# Arduino_DUE_V02b_1.net
KiCad netlist of a schematic drawn in Altium Designer
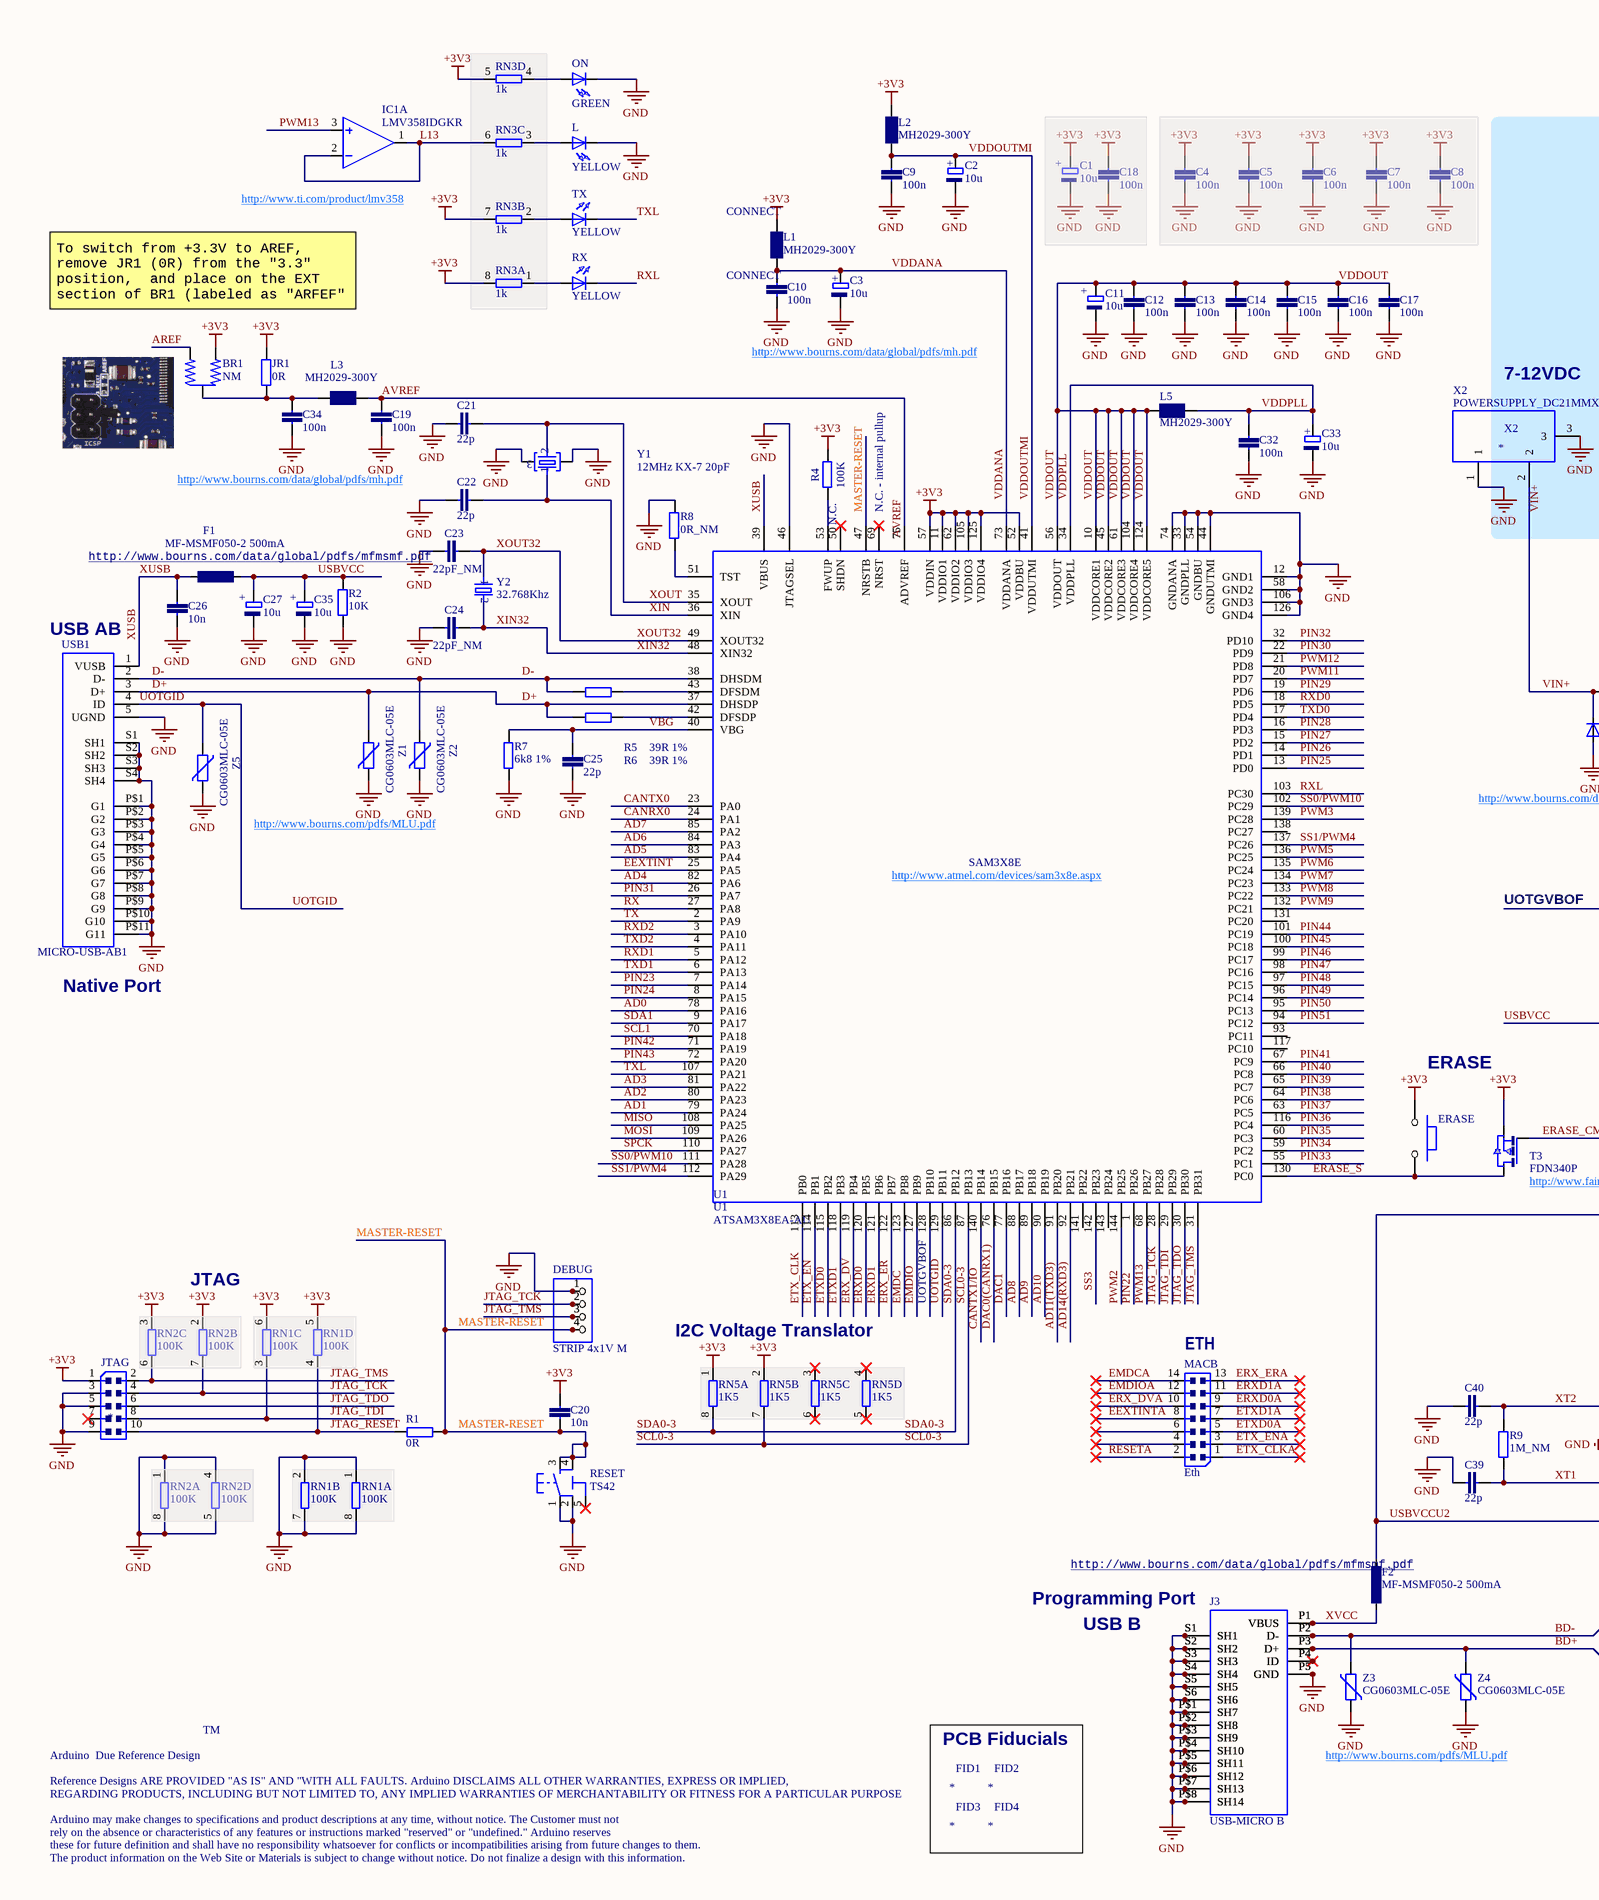
[diagram p0: Arduino_DUE_V02b_1.SchDoc, left]
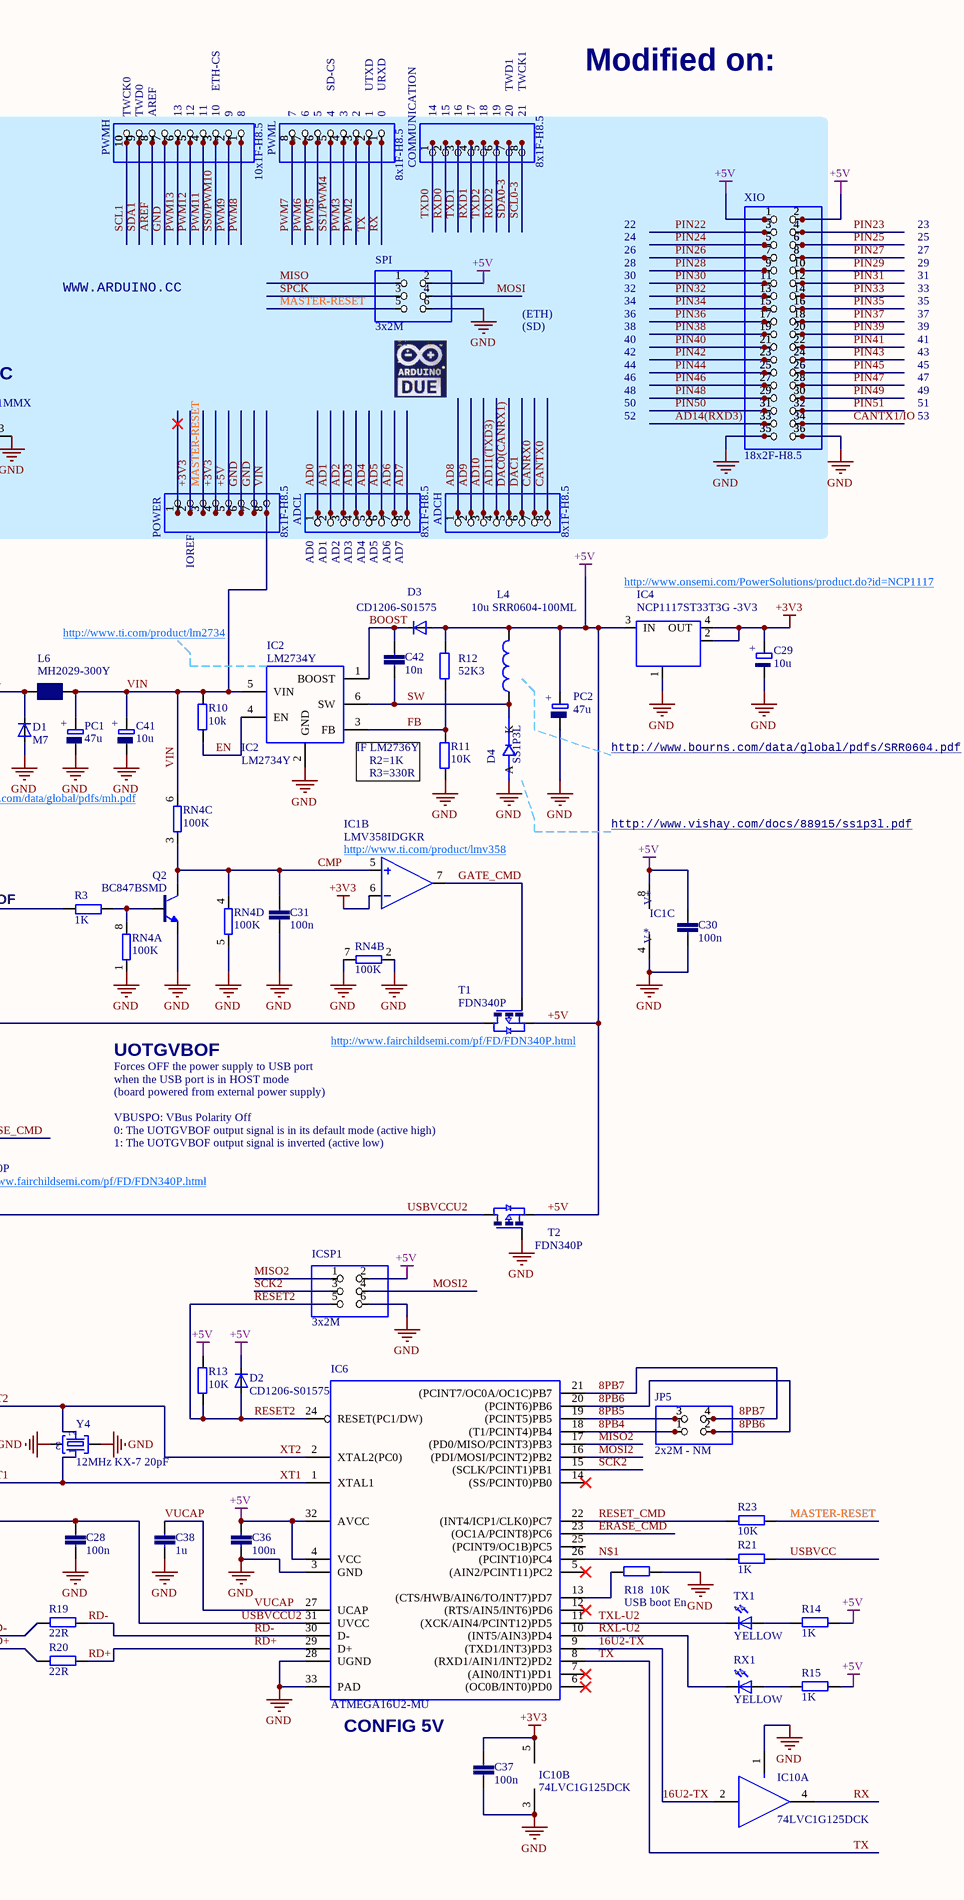
[diagram p1: Arduino_DUE_V02b_1.SchDoc, right]

(export (version "E")
  (design (tool "Eeschema 10.0.6"))
  (components
    (comp (ref "ADCH") (value "8x1F-H8.5") (footprint "1X08") (libsource (lib "SmartPrj") (part "PINHD-1X8")))
    (comp (ref "ADCL") (value "8x1F-H8.5") (footprint "1X08") (libsource (lib "SmartPrj") (part "PINHD-1X8")))
    (comp (ref "BR1") (value "NM") (footprint "J0402") (libsource (lib "bibaja") (part "J0402")))
    (comp (ref "C1") (value "10u") (footprint "SMC_B") (libsource (lib "") (part "CPOL-EUSMCB_1")))
    (comp (ref "C2") (value "10u") (footprint "SMC_B") (libsource (lib "rcl") (part "CPOL-EUSMCB")))
    (comp (ref "C3") (value "10u") (footprint "SMC_B") (libsource (lib "rcl") (part "CPOL-EUSMCB")))
    (comp (ref "C4") (value "100n") (footprint "C0402") (libsource (lib "") (part "C-EUC0402_2")))
    (comp (ref "C5") (value "100n") (footprint "C0402") (libsource (lib "") (part "C-EUC0402_2")))
    (comp (ref "C6") (value "100n") (footprint "C0402") (libsource (lib "") (part "C-EUC0402_2")))
    (comp (ref "C7") (value "100n") (footprint "C0402") (libsource (lib "") (part "C-EUC0402_2")))
    (comp (ref "C8") (value "100n") (footprint "C0402") (libsource (lib "") (part "C-EUC0402_2")))
    (comp (ref "C9") (value "100n") (footprint "C0402") (libsource (lib "") (part "C-EUC0402_2")))
    (comp (ref "C10") (value "100n") (footprint "C0402") (libsource (lib "") (part "C-EUC0402_2")))
    (comp (ref "C11") (value "10u") (footprint "SMC_B") (libsource (lib "") (part "CPOL-EUSMCB_1")))
    (comp (ref "C12") (value "100n") (footprint "C0402") (libsource (lib "") (part "C-EUC0402_2")))
    (comp (ref "C13") (value "100n") (footprint "C0402") (libsource (lib "") (part "C-EUC0402_2")))
    (comp (ref "C14") (value "100n") (footprint "C0402") (libsource (lib "") (part "C-EUC0402_2")))
    (comp (ref "C15") (value "100n") (footprint "C0402") (libsource (lib "") (part "C-EUC0402_2")))
    (comp (ref "C16") (value "100n") (footprint "C0402") (libsource (lib "") (part "C-EUC0402_2")))
    (comp (ref "C17") (value "100n") (footprint "C0402") (libsource (lib "") (part "C-EUC0402_2")))
    (comp (ref "C18") (value "100n") (footprint "C0402") (libsource (lib "") (part "C-EUC0402_2")))
    (comp (ref "C19") (value "100n") (footprint "C0402") (libsource (lib "") (part "C-EUC0402_1")))
    (comp (ref "C20") (value "10n") (footprint "C0402") (libsource (lib "") (part "C-EUC0402_1")))
    (comp (ref "C21") (value "22p") (footprint "C0402") (libsource (lib "") (part "C-EUC0402_3")))
    (comp (ref "C22") (value "22p") (footprint "C0402") (libsource (lib "") (part "C-EUC0402_3")))
    (comp (ref "C23") (value "22pF_NM") (footprint "C0402") (libsource (lib "") (part "C-EUC0402_3")))
    (comp (ref "C24") (value "22pF_NM") (footprint "C0402") (libsource (lib "") (part "C-EUC0402_3")))
    (comp (ref "C25") (value "22p") (footprint "C0402") (libsource (lib "SmartPrj") (part "C-EUC0402")))
    (comp (ref "C26") (value "10n") (footprint "C0402") (libsource (lib "SmartPrj") (part "C-EUC0402")))
    (comp (ref "C27") (value "10u") (footprint "SMC_B") (libsource (lib "") (part "CPOL-EUSMCB_1")))
    (comp (ref "C28") (value "100n") (footprint "C0402") (libsource (lib "SmartPrj") (part "C-EUC0402")))
    (comp (ref "C29") (value "10u") (footprint "SMC_B") (libsource (lib "") (part "CPOL-EUSMCB_1")))
    (comp (ref "C30") (value "100n") (footprint "C0402") (libsource (lib "") (part "C-EUC0402_2")))
    (comp (ref "C31") (value "100n") (footprint "C0402") (libsource (lib "") (part "C-EUC0402_2")))
    (comp (ref "C32") (value "100n") (footprint "C0402") (libsource (lib "") (part "C-EUC0402_2")))
    (comp (ref "C33") (value "10u") (footprint "SMC_B") (libsource (lib "rcl") (part "CPOL-EUSMCB")))
    (comp (ref "C34") (value "100n") (footprint "C0402") (libsource (lib "") (part "C-EUC0402_1")))
    (comp (ref "C35") (value "10u") (footprint "SMC_B") (libsource (lib "") (part "CPOL-EUSMCB_1")))
    (comp (ref "C36") (value "100n") (footprint "C0402") (libsource (lib "SmartPrj") (part "C-EUC0402")))
    (comp (ref "C37") (value "100n") (footprint "C0402") (libsource (lib "SmartPrj") (part "C-EUC0402")))
    (comp (ref "C38") (value "1u") (footprint "C0402") (libsource (lib "SmartPrj") (part "C-EUC0402")))
    (comp (ref "C39") (value "22p") (footprint "C0402") (libsource (lib "") (part "C-EUC0402_3")))
    (comp (ref "C40") (value "22p") (footprint "C0402") (libsource (lib "") (part "C-EUC0402_3")))
    (comp (ref "C41") (value "10u") (footprint "SMC_B") (libsource (lib "") (part "CPOL-EUSMCB_2")))
    (comp (ref "C42") (value "10n") (footprint "C0603-ROUND") (libsource (lib "SmartPrj") (part "C-EUC0603")))
    (comp (ref "COMMUNICATION")
      (value "8x1F-H8.5")
      (footprint "1X08")
      (libsource (lib "SmartPrj") (part "PINHD-1X8"))
    )
    (comp (ref "D1") (value "M7") (footprint "SMB") (libsource (lib "diode") (part "DIODE-SMB")))
    (comp (ref "D2")
      (value "CD1206-S01575")
      (footprint "MINIMELF")
      (libsource (lib "diode") (part "DIODE-MINIMELF"))
    )
    (comp (ref "D3")
      (value "CD1206-S01575")
      (footprint "MINIMELF")
      (libsource (lib "diode") (part "DIODE-MINIMELF"))
    )
    (comp (ref "D4") (value "SS1P3L") (footprint "DO220AAL") (libsource (lib "SmartPrj") (part "SS1P3L")))
    (comp (ref "DEBUG")
      (value "STRIP 4x1V M")
      (footprint "1X04")
      (libsource (lib "pinhead") (part "PINHD-1X4"))
    )
    (comp (ref "ERASE") (value "~") (footprint "SMD_157SW") (libsource (lib "SmartPrj") (part "MYSMD_PB157")))
    (comp (ref "F1")
      (value "MF-MSMF050-2 500mA")
      (footprint "L1812")
      (libsource (lib "rcl") (part "L-EUL1812"))
    )
    (comp (ref "F2")
      (value "MF-MSMF050-2 500mA")
      (footprint "L1812")
      (libsource (lib "") (part "L-EUL1812_1"))
    )
    (comp (ref "FID1")
      (value "*")
      (footprint "FIDUCIA-MOUNT")
      (libsource (lib "SmartPrj") (part "FIDUCIALMOUNT"))
    )
    (comp (ref "FID2")
      (value "*")
      (footprint "FIDUCIA-MOUNT")
      (libsource (lib "SmartPrj") (part "FIDUCIALMOUNT"))
    )
    (comp (ref "FID3")
      (value "*")
      (footprint "FIDUCIA-MOUNT")
      (libsource (lib "SmartPrj") (part "FIDUCIALMOUNT"))
    )
    (comp (ref "FID4")
      (value "*")
      (footprint "FIDUCIA-MOUNT")
      (libsource (lib "SmartPrj") (part "FIDUCIALMOUNT"))
    )
    (comp (ref "IC1") (value "LMV358IDGKR") (footprint "MSOP08") (libsource (lib "") (part "LMV358MMX_1")))
    (comp (ref "IC2") (value "LM2734Y") (footprint "SOT23-6") (libsource (lib "SmartPrj") (part "LM2736Y")))
    (comp (ref "IC4")
      (value "NCP1117ST33T3G -3V3")
      (footprint "SOT223")
      (libsource (lib "linear") (part "MC33269ST-3.3T3"))
    )
    (comp (ref "IC6")
      (value "ATMEGA16U2-MU")
      (footprint "MLF32")
      (libsource (lib "SmartPrj") (part "ATMEGA16U2-MU"))
    )
    (comp (ref "IC10")
      (value "74LVC1G125DCK")
      (footprint "SC70-5")
      (libsource (lib "") (part "74LVC1G125DCK_1"))
    )
    (comp (ref "ICSP1") (value "3x2M") (footprint "2X03") (libsource (lib "SmartPrj") (part "PINHD-2X3")))
    (comp (ref "J3")
      (value "USB-MICRO B")
      (footprint "CON2_USB_MICRO_B_AT")
      (libsource (lib "SmartPrj") (part "MYCON2_USB-MINI-B"))
    )
    (comp (ref "JP5") (value "2x2M - NM") (footprint "2X02") (libsource (lib "SmartPrj") (part "PINHD-2X2")))
    (comp (ref "JR1") (value "0R") (footprint "R0402") (libsource (lib "") (part "R-EU_R0402_2")))
    (comp (ref "JTAG")
      (value "*")
      (footprint "PINHEAD_2X05_127")
      (libsource (lib "Arduino_Wifi_shield_v018_tG") (part "PINHEAD_PINHD-2X5PASSO127"))
    )
    (comp (ref "L")
      (value "YELLOW")
      (footprint "CHIP-LED0805")
      (libsource (lib "") (part "LEDCHIP-LED0805_2"))
    )
    (comp (ref "L1") (value "MH2029-300Y") (footprint "0805") (libsource (lib "") (part "WE-CBF_0805_1")))
    (comp (ref "L2") (value "MH2029-300Y") (footprint "0805") (libsource (lib "") (part "WE-CBF_0805_1")))
    (comp (ref "L3") (value "MH2029-300Y") (footprint "0805") (libsource (lib "") (part "WE-CBF_0805_2")))
    (comp (ref "L4")
      (value "10u SRR0604-100ML")
      (footprint "SRR0604")
      (libsource (lib "SmartPrj") (part "L-USSRR0604"))
    )
    (comp (ref "L5") (value "MH2029-300Y") (footprint "0805") (libsource (lib "") (part "WE-CBF_0805_2")))
    (comp (ref "L6")
      (value "MH2029-300Y")
      (footprint "0805")
      (libsource (lib "wuerth-elektronik") (part "WE-CBF_0805"))
    )
    (comp (ref "MACB")
      (value "Eth")
      (footprint "PINHEAD_2X07_127")
      (libsource (lib "Arduino_Wifi_shield_v018_tG") (part "PINHEAD_PINHD-2X7PASSO127"))
    )
    (comp (ref "ON")
      (value "GREEN")
      (footprint "CHIP-LED0805")
      (libsource (lib "") (part "LEDCHIP-LED0805_2"))
    )
    (comp (ref "PC1") (value "47u") (footprint "PANASONIC_D") (libsource (lib "rcl") (part "CPOL-EUD")))
    (comp (ref "PC2") (value "47u") (footprint "PANASONIC_D") (libsource (lib "rcl") (part "CPOL-EUD")))
    (comp (ref "POWER")
      (value "8x1F-H8.5")
      (footprint "1X08")
      (libsource (lib "SmartPrj") (part "PINHD-1X8"))
    )
    (comp (ref "PWMH")
      (value "10x1F-H8.5")
      (footprint "1X10")
      (libsource (lib "SmartPrj") (part "PINHD-1X10"))
    )
    (comp (ref "PWML") (value "8x1F-H8.5") (footprint "1X08") (libsource (lib "SmartPrj") (part "PINHD-1X8")))
    (comp (ref "Q2")
      (value "BC847BSMD")
      (footprint "SOT23")
      (libsource (lib "transistor-npn") (part "BC847BSMD"))
    )
    (comp (ref "R1") (value "0R") (footprint "R0402") (libsource (lib "") (part "R-EU_R0402_2")))
    (comp (ref "R2") (value "10K") (footprint "R0402") (libsource (lib "") (part "R-EU_R0402_1")))
    (comp (ref "R3") (value "1K") (footprint "R0402") (libsource (lib "") (part "R-EU_R0402_2")))
    (comp (ref "R4") (value "100K") (footprint "R0402") (libsource (lib "SmartPrj") (part "R-EU_R0402")))
    (comp (ref "R5") (value "39R 1%") (footprint "R0402") (libsource (lib "") (part "R-EU_R0402_2")))
    (comp (ref "R6") (value "39R 1%") (footprint "R0402") (libsource (lib "") (part "R-EU_R0402_2")))
    (comp (ref "R7")
      (value "6k8 1%")
      (footprint "R0603-ROUND")
      (libsource (lib "SmartPrj") (part "R-EU_R0603"))
    )
    (comp (ref "R8") (value "0R_NM") (footprint "R0402") (libsource (lib "") (part "R-EU_R0402_2")))
    (comp (ref "R9") (value "1M_NM") (footprint "R0402") (libsource (lib "SmartPrj") (part "R-EU_R0402")))
    (comp (ref "R10") (value "10k") (footprint "R0402") (libsource (lib "") (part "R-EU_R0402_2")))
    (comp (ref "R11")
      (value "10K")
      (footprint "R0603-ROUND")
      (libsource (lib "SmartPrj") (part "R-EU_0603-RND"))
    )
    (comp (ref "R12")
      (value "52K3")
      (footprint "R0603-ROUND")
      (libsource (lib "SmartPrj") (part "R-EU_0603-RND"))
    )
    (comp (ref "R13") (value "10K") (footprint "R0402") (libsource (lib "SmartPrj") (part "R-EU_R0402")))
    (comp (ref "R14") (value "1K") (footprint "R0402") (libsource (lib "") (part "R-EU_R0402_2")))
    (comp (ref "R15") (value "1K") (footprint "R0402") (libsource (lib "") (part "R-EU_R0402_2")))
    (comp (ref "R18") (value "10K") (footprint "R0402") (libsource (lib "SmartPrj") (part "R-EU_R0402")))
    (comp (ref "R19") (value "22R") (footprint "R0402") (libsource (lib "") (part "R-EU_R0402_2")))
    (comp (ref "R20") (value "22R") (footprint "R0402") (libsource (lib "") (part "R-EU_R0402_2")))
    (comp (ref "R21") (value "1K") (footprint "R0402") (libsource (lib "SmartPrj") (part "R-EU_R0402")))
    (comp (ref "R23") (value "10K") (footprint "R0402") (libsource (lib "SmartPrj") (part "R-EU_R0402")))
    (comp (ref "RESET") (value "TS42") (footprint "TS42") (libsource (lib "SmartPrj") (part "TS42")))
    (comp (ref "RN1") (value "100K") (footprint "CAT16") (libsource (lib "") (part "4R-NCAT16_14")))
    (comp (ref "RN2") (value "100K") (footprint "CAT16") (libsource (lib "") (part "4R-NCAT16_10")))
    (comp (ref "RN3") (value "1k") (footprint "CAY16") (libsource (lib "") (part "4R-NCAY16_2")))
    (comp (ref "RN4") (value "100K") (footprint "CAT16") (libsource (lib "") (part "4R-NCAT16_11")))
    (comp (ref "RN5") (value "1K5") (footprint "CAT16") (libsource (lib "") (part "4R-NCAT16_5")))
    (comp (ref "RX")
      (value "YELLOW")
      (footprint "CHIP-LED0805")
      (libsource (lib "led") (part "LEDCHIP-LED0805"))
    )
    (comp (ref "RX1")
      (value "YELLOW")
      (footprint "CHIP-LED0805")
      (libsource (lib "") (part "LEDCHIP-LED0805_1"))
    )
    (comp (ref "SPI") (value "3x2M") (footprint "2X03") (libsource (lib "SmartPrj") (part "PINHD-2X3")))
    (comp (ref "T1") (value "FDN340P") (footprint "SOT-23") (libsource (lib "zetex") (part "PMOSSOT23")))
    (comp (ref "T2") (value "FDN340P") (footprint "SOT-23") (libsource (lib "") (part "PMOSSOT23_2")))
    (comp (ref "T3") (value "FDN340P") (footprint "SOT-23") (libsource (lib "") (part "PMOSSOT23_1")))
    (comp (ref "TX")
      (value "YELLOW")
      (footprint "CHIP-LED0805")
      (libsource (lib "led") (part "LEDCHIP-LED0805"))
    )
    (comp (ref "TX1")
      (value "YELLOW")
      (footprint "CHIP-LED0805")
      (libsource (lib "") (part "LEDCHIP-LED0805_1"))
    )
    (comp (ref "U1")
      (value "SAM3X8E")
      (footprint "LQFP144")
      (libsource (lib "SmartPrj") (part "ATSAM3X/AAU"))
    )
    (comp (ref "USB1")
      (value "MICRO-USB-AB1")
      (footprint "MCR-AB1-S-RA-SMT")
      (libsource (lib "SmartPrj") (part "MICRO_USB"))
    )
    (comp (ref "X2")
      (value "*")
      (footprint "POWERSUPPLY_DC-21MM")
      (libsource (lib "SmartPrj") (part "POWERSUPPLY_DC21MMX"))
    )
    (comp (ref "XIO")
      (value "18x2F-H8.5")
      (footprint "2X18")
      (libsource (lib "SmartPrj") (part "PINHD-2X18"))
    )
    (comp (ref "Y1")
      (value "12MHz KX-7 20pF")
      (footprint "CRYSTAL-3.2-2.5")
      (libsource (lib "") (part "CRYSTAL-3.2-2.5_1"))
    )
    (comp (ref "Y2")
      (value "32.768Khz")
      (footprint "RESONATOR_EPSON_FC_145")
      (libsource (lib "Arduino_Wifi_shield_v018_tG") (part "RESONATOR_EPSON_FC_145"))
    )
    (comp (ref "Y4")
      (value "12MHz KX-7 20pF")
      (footprint "CRYSTAL-3.2-2.5")
      (libsource (lib "SmartPrj") (part "CRYSTAL-3.2-2.5"))
    )
    (comp (ref "Z1")
      (value "CG0603MLC-05E")
      (footprint "CT/CN0603")
      (libsource (lib "varistor") (part "VARISTORCN0603"))
    )
    (comp (ref "Z2")
      (value "CG0603MLC-05E")
      (footprint "CT/CN0603")
      (libsource (lib "varistor") (part "VARISTORCN0603"))
    )
    (comp (ref "Z3")
      (value "CG0603MLC-05E")
      (footprint "CT/CN0603")
      (libsource (lib "") (part "VARISTORCN0603_1"))
    )
    (comp (ref "Z4")
      (value "CG0603MLC-05E")
      (footprint "CT/CN0603")
      (libsource (lib "") (part "VARISTORCN0603_1"))
    )
    (comp (ref "Z5")
      (value "CG0603MLC-05E")
      (footprint "CT/CN0603")
      (libsource (lib "varistor") (part "VARISTORCN0603"))
    )
  )
  (nets
    (net (code "1") (name "+3V3") (class "Default")
      (node (ref "BR1") (pin "3") (pinfunction "2_3") (pintype "passive"))
      (node (ref "C1") (pin "+") (pinfunction "+_+") (pintype "passive"))
      (node (ref "C18") (pin "2") (pinfunction "2_2") (pintype "passive"))
      (node (ref "C20") (pin "2") (pinfunction "2_2") (pintype "passive"))
      (node (ref "C29") (pin "+") (pinfunction "+_+") (pintype "passive"))
      (node (ref "C37") (pin "1") (pinfunction "1_1") (pintype "passive"))
      (node (ref "C4") (pin "2") (pinfunction "2_2") (pintype "passive"))
      (node (ref "C5") (pin "2") (pinfunction "2_2") (pintype "passive"))
      (node (ref "C6") (pin "2") (pinfunction "2_2") (pintype "passive"))
      (node (ref "C7") (pin "2") (pinfunction "2_2") (pintype "passive"))
      (node (ref "C8") (pin "2") (pinfunction "2_2") (pintype "passive"))
      (node (ref "ERASE") (pin "1") (pinfunction "1_1") (pintype "passive"))
      (node (ref "IC1") (pin "6") (pinfunction "-IN_6") (pintype "passive"))
      (node (ref "IC10") (pin "5") (pinfunction "VCC_5") (pintype "passive"))
      (node (ref "IC4") (pin "2") (pinfunction "OUT@1_2") (pintype "passive"))
      (node (ref "IC4") (pin "4") (pinfunction "OUT_4") (pintype "passive"))
      (node (ref "JR1") (pin "1") (pinfunction "1_1") (pintype "passive"))
      (node (ref "JTAG") (pin "1") (pinfunction "1_1") (pintype "passive"))
      (node (ref "L1") (pin "1") (pinfunction "1_1") (pintype "passive"))
      (node (ref "L2") (pin "1") (pinfunction "1_1") (pintype "passive"))
      (node (ref "POWER") (pin "2") (pinfunction "2_2") (pintype "passive"))
      (node (ref "POWER") (pin "4") (pinfunction "4_4") (pintype "passive"))
      (node (ref "R4") (pin "2") (pinfunction "2_2") (pintype "passive"))
      (node (ref "RN1") (pin "5") (pinfunction "2_5") (pintype "passive"))
      (node (ref "RN1") (pin "6") (pinfunction "2_6") (pintype "passive"))
      (node (ref "RN2") (pin "2") (pinfunction "1_2") (pintype "passive"))
      (node (ref "RN2") (pin "3") (pinfunction "1_3") (pintype "passive"))
      (node (ref "RN3") (pin "5") (pinfunction "2_5") (pintype "passive"))
      (node (ref "RN3") (pin "7") (pinfunction "2_7") (pintype "passive"))
      (node (ref "RN3") (pin "8") (pinfunction "2_8") (pintype "passive"))
      (node (ref "RN5") (pin "1") (pinfunction "1_1") (pintype "passive"))
      (node (ref "RN5") (pin "2") (pinfunction "1_2") (pintype "passive"))
      (node (ref "T3") (pin "2") (pinfunction "S_2") (pintype "passive"))
      (node (ref "U1") (pin "105") (pinfunction "VDDIO3_105") (pintype "passive"))
      (node (ref "U1") (pin "11") (pinfunction "VDDIO1_11") (pintype "passive"))
      (node (ref "U1") (pin "125") (pinfunction "VDDIO4_125") (pintype "passive"))
      (node (ref "U1") (pin "52") (pinfunction "VDDBU_52") (pintype "passive"))
      (node (ref "U1") (pin "57") (pinfunction "VDDIN_57") (pintype "passive"))
      (node (ref "U1") (pin "62") (pinfunction "VDDIO2_62") (pintype "passive"))
    )
    (net (code "2") (name "+5V") (class "Default")
      (node (ref "C30") (pin "2") (pinfunction "2_2") (pintype "passive"))
      (node (ref "C36") (pin "1") (pinfunction "1_1") (pintype "passive"))
      (node (ref "D2") (pin "C") (pinfunction "C_C") (pintype "passive"))
      (node (ref "D3") (pin "A") (pinfunction "A_A") (pintype "passive"))
      (node (ref "IC1") (pin "8") (pinfunction "V+_8") (pintype "passive"))
      (node (ref "IC4") (pin "3") (pinfunction "IN_3") (pintype "passive"))
      (node (ref "IC6") (pin "32") (pinfunction "AVCC_32") (pintype "passive"))
      (node (ref "IC6") (pin "4") (pinfunction "VCC_4") (pintype "passive"))
      (node (ref "ICSP1") (pin "2") (pinfunction "2_2") (pintype "passive"))
      (node (ref "L4") (pin "P$2") (pinfunction "2_P$2") (pintype "passive"))
      (node (ref "PC2") (pin "+") (pinfunction "+_+") (pintype "passive"))
      (node (ref "POWER") (pin "5") (pinfunction "5_5") (pintype "passive"))
      (node (ref "R12") (pin "1") (pinfunction "1_1") (pintype "passive"))
      (node (ref "R13") (pin "2") (pinfunction "2_2") (pintype "passive"))
      (node (ref "R14") (pin "1") (pinfunction "1_1") (pintype "passive"))
      (node (ref "R15") (pin "1") (pinfunction "1_1") (pintype "passive"))
      (node (ref "SPI") (pin "2") (pinfunction "2_2") (pintype "passive"))
      (node (ref "T1") (pin "2") (pinfunction "S_2") (pintype "passive"))
      (node (ref "T2") (pin "2") (pinfunction "S_2") (pintype "passive"))
      (node (ref "XIO") (pin "1") (pinfunction "1_1") (pintype "passive"))
      (node (ref "XIO") (pin "2") (pinfunction "2_2") (pintype "passive"))
    )
    (net (code "3") (name "/8PB4") (class "Default")
      (node (ref "IC6") (pin "18") (pinfunction "(T1/PCINT4)PB4_18") (pintype "passive"))
      (node (ref "JP5") (pin "1") (pinfunction "1_1") (pintype "passive"))
    )
    (net (code "4") (name "/8PB5") (class "Default")
      (node (ref "IC6") (pin "19") (pinfunction "(PCINT5)PB5_19") (pintype "passive"))
      (node (ref "JP5") (pin "3") (pinfunction "3_3") (pintype "passive"))
    )
    (net (code "5") (name "/8PB6") (class "Default")
      (node (ref "IC6") (pin "20") (pinfunction "(PCINT6)PB6_20") (pintype "passive"))
      (node (ref "JP5") (pin "2") (pinfunction "2_2") (pintype "passive"))
    )
    (net (code "6") (name "/8PB7") (class "Default")
      (node (ref "IC6") (pin "21") (pinfunction "(PCINT7/OC0A/OC1C)PB7_21") (pintype "passive"))
      (node (ref "JP5") (pin "4") (pinfunction "4_4") (pintype "passive"))
    )
    (net (code "7") (name "/16U2-TX") (class "Default")
      (node (ref "IC10") (pin "2") (pinfunction "I_2") (pintype "passive"))
      (node (ref "IC6") (pin "9") (pinfunction "(TXD1/INT3)PD3_9") (pintype "passive"))
    )
    (net (code "8") (name "/AD0") (class "Default")
      (node (ref "ADCL") (pin "1") (pinfunction "1_1") (pintype "passive"))
      (node (ref "U1") (pin "78") (pinfunction "PA16_78") (pintype "passive"))
    )
    (net (code "9") (name "/AD1") (class "Default")
      (node (ref "ADCL") (pin "2") (pinfunction "2_2") (pintype "passive"))
      (node (ref "U1") (pin "79") (pinfunction "PA24_79") (pintype "passive"))
    )
    (net (code "10") (name "/AD2") (class "Default")
      (node (ref "ADCL") (pin "3") (pinfunction "3_3") (pintype "passive"))
      (node (ref "U1") (pin "80") (pinfunction "PA23_80") (pintype "passive"))
    )
    (net (code "11") (name "/AD3") (class "Default")
      (node (ref "ADCL") (pin "4") (pinfunction "4_4") (pintype "passive"))
      (node (ref "U1") (pin "81") (pinfunction "PA22_81") (pintype "passive"))
    )
    (net (code "12") (name "/AD4") (class "Default")
      (node (ref "ADCL") (pin "5") (pinfunction "5_5") (pintype "passive"))
      (node (ref "U1") (pin "82") (pinfunction "PA6_82") (pintype "passive"))
    )
    (net (code "13") (name "/AD5") (class "Default")
      (node (ref "ADCL") (pin "6") (pinfunction "6_6") (pintype "passive"))
      (node (ref "U1") (pin "83") (pinfunction "PA4_83") (pintype "passive"))
    )
    (net (code "14") (name "/AD6") (class "Default")
      (node (ref "ADCL") (pin "7") (pinfunction "7_7") (pintype "passive"))
      (node (ref "U1") (pin "84") (pinfunction "PA3_84") (pintype "passive"))
    )
    (net (code "15") (name "/AD7") (class "Default")
      (node (ref "ADCL") (pin "8") (pinfunction "8_8") (pintype "passive"))
      (node (ref "U1") (pin "85") (pinfunction "PA2_85") (pintype "passive"))
    )
    (net (code "16") (name "/AD8") (class "Default")
      (node (ref "ADCH") (pin "1") (pinfunction "1_1") (pintype "passive"))
      (node (ref "U1") (pin "88") (pinfunction "PB17_88") (pintype "passive"))
    )
    (net (code "17") (name "/AD9") (class "Default")
      (node (ref "ADCH") (pin "2") (pinfunction "2_2") (pintype "passive"))
      (node (ref "U1") (pin "89") (pinfunction "PB18_89") (pintype "passive"))
    )
    (net (code "18") (name "/AD10") (class "Default")
      (node (ref "ADCH") (pin "3") (pinfunction "3_3") (pintype "passive"))
      (node (ref "U1") (pin "90") (pinfunction "PB19_90") (pintype "passive"))
    )
    (net (code "19") (name "/AD11(TXD3)") (class "Default")
      (node (ref "ADCH") (pin "4") (pinfunction "4_4") (pintype "passive"))
      (node (ref "U1") (pin "91") (pinfunction "PB20_91") (pintype "passive"))
    )
    (net (code "20") (name "/AD14(RXD3)") (class "Default")
      (node (ref "U1") (pin "92") (pinfunction "PB21_92") (pintype "passive"))
      (node (ref "XIO") (pin "33") (pinfunction "33_33") (pintype "passive"))
    )
    (net (code "21") (name "/AREF") (class "Default")
      (node (ref "BR1") (pin "1") (pinfunction "1_1") (pintype "passive"))
      (node (ref "PWMH") (pin "8") (pinfunction "8_8") (pintype "passive"))
    )
    (net (code "22") (name "/AVREF") (class "Default")
      (node (ref "C19") (pin "2") (pinfunction "2_2") (pintype "passive"))
      (node (ref "L3") (pin "2") (pinfunction "2_2") (pintype "passive"))
      (node (ref "U1") (pin "75") (pinfunction "ADVREF_75") (pintype "passive"))
    )
    (net (code "23") (name "/BD+") (class "Default")
      (node (ref "J3") (pin "P3") (pinfunction "D+_P3") (pintype "passive"))
      (node (ref "R20") (pin "2") (pinfunction "2_2") (pintype "passive"))
      (node (ref "Z4") (pin "2") (pinfunction "2_2") (pintype "passive"))
    )
    (net (code "24") (name "/BD-") (class "Default")
      (node (ref "J3") (pin "P2") (pinfunction "D-_P2") (pintype "passive"))
      (node (ref "R19") (pin "2") (pinfunction "2_2") (pintype "passive"))
      (node (ref "Z3") (pin "2") (pinfunction "2_2") (pintype "passive"))
    )
    (net (code "25") (name "/BOOST") (class "Default")
      (node (ref "C42") (pin "1") (pinfunction "1_1") (pintype "passive"))
      (node (ref "D3") (pin "C") (pinfunction "C_C") (pintype "passive"))
      (node (ref "IC2") (pin "1") (pinfunction "BOOST_1") (pintype "passive"))
    )
    (net (code "26") (name "/CANRX0") (class "Default")
      (node (ref "ADCH") (pin "7") (pinfunction "7_7") (pintype "passive"))
      (node (ref "U1") (pin "24") (pinfunction "PA1_24") (pintype "passive"))
    )
    (net (code "27") (name "/CANTX0") (class "Default")
      (node (ref "ADCH") (pin "8") (pinfunction "8_8") (pintype "passive"))
      (node (ref "U1") (pin "23") (pinfunction "PA0_23") (pintype "passive"))
    )
    (net (code "28") (name "/CANTX1{slash}IO") (class "Default")
      (node (ref "U1") (pin "140") (pinfunction "PB14_140") (pintype "passive"))
      (node (ref "XIO") (pin "34") (pinfunction "34_34") (pintype "passive"))
    )
    (net (code "29") (name "/CMP") (class "Default")
      (node (ref "C31") (pin "2") (pinfunction "2_2") (pintype "passive"))
      (node (ref "IC1") (pin "5") (pinfunction "+IN_5") (pintype "passive"))
      (node (ref "Q2") (pin "3") (pinfunction "C_3") (pintype "passive"))
      (node (ref "RN4") (pin "3") (pinfunction "1_3") (pintype "passive"))
      (node (ref "RN4") (pin "4") (pinfunction "1_4") (pintype "passive"))
    )
    (net (code "30") (name "/D+") (class "Default")
      (node (ref "R6") (pin "1") (pinfunction "1_1") (pintype "passive"))
      (node (ref "U1") (pin "37") (pinfunction "DHSDP_37") (pintype "passive"))
      (node (ref "USB1") (pin "3") (pinfunction "D+_3") (pintype "passive"))
      (node (ref "Z1") (pin "1") (pinfunction "1_1") (pintype "passive"))
    )
    (net (code "31") (name "/D-") (class "Default")
      (node (ref "R5") (pin "1") (pinfunction "1_1") (pintype "passive"))
      (node (ref "U1") (pin "38") (pinfunction "DHSDM_38") (pintype "passive"))
      (node (ref "USB1") (pin "2") (pinfunction "D-_2") (pintype "passive"))
      (node (ref "Z2") (pin "1") (pinfunction "1_1") (pintype "passive"))
    )
    (net (code "32") (name "/DAC0(CANRX1)") (class "Default")
      (node (ref "ADCH") (pin "5") (pinfunction "5_5") (pintype "passive"))
      (node (ref "U1") (pin "76") (pinfunction "PB15_76") (pintype "passive"))
    )
    (net (code "33") (name "/DAC1") (class "Default")
      (node (ref "ADCH") (pin "6") (pinfunction "6_6") (pintype "passive"))
      (node (ref "U1") (pin "77") (pinfunction "PB16_77") (pintype "passive"))
    )
    (net (code "34") (name "/EEXTINT") (class "Default")
      (node (ref "U1") (pin "25") (pinfunction "PA5_25") (pintype "passive"))
    )
    (net (code "35") (name "/EEXTINTA") (class "Default")
      (node (ref "MACB") (pin "8") (pinfunction "8_8") (pintype "passive+no_connect"))
    )
    (net (code "36") (name "/EMDC") (class "Default")
      (node (ref "U1") (pin "123") (pinfunction "PB8_123") (pintype "passive"))
    )
    (net (code "37") (name "/EMDCA") (class "Default")
      (node (ref "MACB") (pin "14") (pinfunction "14_14") (pintype "passive+no_connect"))
    )
    (net (code "38") (name "/EMDIO") (class "Default")
      (node (ref "U1") (pin "127") (pinfunction "PB9_127") (pintype "passive"))
    )
    (net (code "39") (name "/EMDIOA") (class "Default")
      (node (ref "MACB") (pin "12") (pinfunction "13_12") (pintype "passive+no_connect"))
    )
    (net (code "40") (name "/EN") (class "Default")
      (node (ref "IC2") (pin "4") (pinfunction "EN_4") (pintype "passive"))
      (node (ref "R10") (pin "2") (pinfunction "2_2") (pintype "passive"))
    )
    (net (code "41") (name "/ERASE_CMD") (class "Default")
      (node (ref "IC6") (pin "23") (pinfunction "(OC1A/PCINT8)PC6_23") (pintype "passive"))
      (node (ref "T3") (pin "3") (pinfunction "G_3") (pintype "passive"))
    )
    (net (code "42") (name "/ERASE_S") (class "Default")
      (node (ref "ERASE") (pin "2") (pinfunction "2_2") (pintype "passive"))
      (node (ref "T3") (pin "1") (pinfunction "D_1") (pintype "passive"))
      (node (ref "U1") (pin "130") (pinfunction "PC0_130") (pintype "passive"))
    )
    (net (code "43") (name "/ERXD0") (class "Default")
      (node (ref "U1") (pin "120") (pinfunction "PB5_120") (pintype "passive"))
    )
    (net (code "44") (name "/ERXD0A") (class "Default")
      (node (ref "MACB") (pin "9") (pinfunction "9_9") (pintype "passive+no_connect"))
    )
    (net (code "45") (name "/ERXD1") (class "Default")
      (node (ref "U1") (pin "121") (pinfunction "PB6_121") (pintype "passive"))
    )
    (net (code "46") (name "/ERXD1A") (class "Default")
      (node (ref "MACB") (pin "11") (pinfunction "11_11") (pintype "passive+no_connect"))
    )
    (net (code "47") (name "/ERX_DV") (class "Default")
      (node (ref "U1") (pin "119") (pinfunction "PB4_119") (pintype "passive"))
    )
    (net (code "48") (name "/ERX_DVA") (class "Default")
      (node (ref "MACB") (pin "10") (pinfunction "10_10") (pintype "passive+no_connect"))
    )
    (net (code "49") (name "/ERX_ER") (class "Default")
      (node (ref "U1") (pin "122") (pinfunction "PB7_122") (pintype "passive"))
    )
    (net (code "50") (name "/ERX_ERA") (class "Default")
      (node (ref "MACB") (pin "13") (pinfunction "12_13") (pintype "passive+no_connect"))
    )
    (net (code "51") (name "/ETXD0") (class "Default")
      (node (ref "U1") (pin "115") (pinfunction "PB2_115") (pintype "passive"))
    )
    (net (code "52") (name "/ETXD0A") (class "Default")
      (node (ref "MACB") (pin "5") (pinfunction "5_5") (pintype "passive+no_connect"))
    )
    (net (code "53") (name "/ETXD1") (class "Default")
      (node (ref "U1") (pin "118") (pinfunction "PB3_118") (pintype "passive"))
    )
    (net (code "54") (name "/ETXD1A") (class "Default")
      (node (ref "MACB") (pin "7") (pinfunction "7_7") (pintype "passive+no_connect"))
    )
    (net (code "55") (name "/ETX_CLK") (class "Default")
      (node (ref "U1") (pin "113") (pinfunction "PB0_113") (pintype "passive"))
    )
    (net (code "56") (name "/ETX_CLKA") (class "Default")
      (node (ref "MACB") (pin "1") (pinfunction "1_1") (pintype "passive+no_connect"))
    )
    (net (code "57") (name "/ETX_EN") (class "Default")
      (node (ref "U1") (pin "114") (pinfunction "PB1_114") (pintype "passive"))
    )
    (net (code "58") (name "/ETX_ENA") (class "Default")
      (node (ref "MACB") (pin "3") (pinfunction "3_3") (pintype "passive+no_connect"))
    )
    (net (code "59") (name "/FB") (class "Default")
      (node (ref "IC2") (pin "3") (pinfunction "FB_3") (pintype "passive"))
      (node (ref "R11") (pin "1") (pinfunction "1_1") (pintype "passive"))
      (node (ref "R12") (pin "2") (pinfunction "2_2") (pintype "passive"))
    )
    (net (code "60") (name "/GATE_CMD") (class "Default")
      (node (ref "IC1") (pin "7") (pinfunction "OUT_7") (pintype "passive"))
      (node (ref "T1") (pin "3") (pinfunction "G_3") (pintype "passive"))
    )
    (net (code "61") (name "/JTAG_RESET") (class "Default")
      (node (ref "JTAG") (pin "10") (pinfunction "10_10") (pintype "passive"))
      (node (ref "R1") (pin "1") (pinfunction "1_1") (pintype "passive"))
      (node (ref "RN1") (pin "4") (pinfunction "1_4") (pintype "passive"))
    )
    (net (code "62") (name "/JTAG_TCK") (class "Default")
      (node (ref "DEBUG") (pin "2") (pinfunction "2_2") (pintype "passive"))
      (node (ref "JTAG") (pin "4") (pinfunction "4_4") (pintype "passive"))
      (node (ref "RN2") (pin "7") (pinfunction "2_7") (pintype "passive"))
      (node (ref "U1") (pin "28") (pinfunction "PB28_28") (pintype "passive"))
    )
    (net (code "63") (name "/JTAG_TDI") (class "Default")
      (node (ref "JTAG") (pin "8") (pinfunction "8_8") (pintype "passive"))
      (node (ref "RN1") (pin "3") (pinfunction "1_3") (pintype "passive"))
      (node (ref "U1") (pin "29") (pinfunction "PB29_29") (pintype "passive"))
    )
    (net (code "64") (name "/JTAG_TDO") (class "Default")
      (node (ref "JTAG") (pin "6") (pinfunction "6_6") (pintype "passive"))
      (node (ref "U1") (pin "30") (pinfunction "PB30_30") (pintype "passive"))
    )
    (net (code "65") (name "/JTAG_TMS") (class "Default")
      (node (ref "DEBUG") (pin "3") (pinfunction "3_3") (pintype "passive"))
      (node (ref "JTAG") (pin "2") (pinfunction "2_2") (pintype "passive"))
      (node (ref "RN2") (pin "6") (pinfunction "2_6") (pintype "passive"))
      (node (ref "U1") (pin "31") (pinfunction "PB31_31") (pintype "passive"))
    )
    (net (code "66") (name "/L13") (class "Default")
      (node (ref "IC1") (pin "1") (pinfunction "OUT_1") (pintype "passive"))
      (node (ref "IC1") (pin "2") (pinfunction "-IN_2") (pintype "passive"))
      (node (ref "RN3") (pin "6") (pinfunction "2_6") (pintype "passive"))
    )
    (net (code "67") (name "/MASTER-RESET") (class "Default")
      (node (ref "C20") (pin "1") (pinfunction "1_1") (pintype "passive"))
      (node (ref "DEBUG") (pin "4") (pinfunction "4_4") (pintype "passive"))
      (node (ref "POWER") (pin "3") (pinfunction "3_3") (pintype "passive"))
      (node (ref "R1") (pin "2") (pinfunction "2_2") (pintype "passive"))
      (node (ref "R23") (pin "2") (pinfunction "2_2") (pintype "passive"))
      (node (ref "RESET") (pin "3") (pinfunction "3_3") (pintype "passive"))
      (node (ref "RESET") (pin "4") (pinfunction "4_4") (pintype "passive"))
      (node (ref "SPI") (pin "5") (pinfunction "5_5") (pintype "passive"))
      (node (ref "U1") (pin "47") (pinfunction "NRSTB_47") (pintype "passive"))
    )
    (net (code "68") (name "/MISO") (class "Default")
      (node (ref "SPI") (pin "1") (pinfunction "1_1") (pintype "passive"))
      (node (ref "U1") (pin "108") (pinfunction "PA25_108") (pintype "passive"))
    )
    (net (code "69") (name "/MISO2") (class "Default")
      (node (ref "IC6") (pin "17") (pinfunction "(PD0/MISO/PCINT3)PB3_17") (pintype "passive"))
      (node (ref "ICSP1") (pin "1") (pinfunction "1_1") (pintype "passive"))
    )
    (net (code "70") (name "/MOSI") (class "Default")
      (node (ref "SPI") (pin "4") (pinfunction "4_4") (pintype "passive"))
      (node (ref "U1") (pin "109") (pinfunction "PA26_109") (pintype "passive"))
    )
    (net (code "71") (name "/MOSI2") (class "Default")
      (node (ref "IC6") (pin "16") (pinfunction "(PDI/MOSI/PCINT2)PB2_16") (pintype "passive"))
      (node (ref "ICSP1") (pin "4") (pinfunction "4_4") (pintype "passive"))
    )
    (net (code "72") (name "/N$1") (class "Default")
      (node (ref "IC6") (pin "26") (pinfunction "(PCINT10)PC4_26") (pintype "passive"))
      (node (ref "R21") (pin "1") (pinfunction "1_1") (pintype "passive"))
    )
    (net (code "73") (name "/PIN22") (class "Default")
      (node (ref "U1") (pin "1") (pinfunction "PB26_1") (pintype "passive"))
      (node (ref "XIO") (pin "3") (pinfunction "3_3") (pintype "passive"))
    )
    (net (code "74") (name "/PIN23") (class "Default")
      (node (ref "U1") (pin "7") (pinfunction "PA14_7") (pintype "passive"))
      (node (ref "XIO") (pin "4") (pinfunction "4_4") (pintype "passive"))
    )
    (net (code "75") (name "/PIN24") (class "Default")
      (node (ref "U1") (pin "8") (pinfunction "PA15_8") (pintype "passive"))
      (node (ref "XIO") (pin "5") (pinfunction "5_5") (pintype "passive"))
    )
    (net (code "76") (name "/PIN25") (class "Default")
      (node (ref "U1") (pin "13") (pinfunction "PD0_13") (pintype "passive"))
      (node (ref "XIO") (pin "6") (pinfunction "6_6") (pintype "passive"))
    )
    (net (code "77") (name "/PIN26") (class "Default")
      (node (ref "U1") (pin "14") (pinfunction "PD1_14") (pintype "passive"))
      (node (ref "XIO") (pin "7") (pinfunction "7_7") (pintype "passive"))
    )
    (net (code "78") (name "/PIN27") (class "Default")
      (node (ref "U1") (pin "15") (pinfunction "PD2_15") (pintype "passive"))
      (node (ref "XIO") (pin "8") (pinfunction "8_8") (pintype "passive"))
    )
    (net (code "79") (name "/PIN28") (class "Default")
      (node (ref "U1") (pin "16") (pinfunction "PD3_16") (pintype "passive"))
      (node (ref "XIO") (pin "9") (pinfunction "9_9") (pintype "passive"))
    )
    (net (code "80") (name "/PIN29") (class "Default")
      (node (ref "U1") (pin "19") (pinfunction "PD6_19") (pintype "passive"))
      (node (ref "XIO") (pin "10") (pinfunction "10_10") (pintype "passive"))
    )
    (net (code "81") (name "/PIN30") (class "Default")
      (node (ref "U1") (pin "22") (pinfunction "PD9_22") (pintype "passive"))
      (node (ref "XIO") (pin "11") (pinfunction "11_11") (pintype "passive"))
    )
    (net (code "82") (name "/PIN31") (class "Default")
      (node (ref "U1") (pin "26") (pinfunction "PA7_26") (pintype "passive"))
      (node (ref "XIO") (pin "12") (pinfunction "12_12") (pintype "passive"))
    )
    (net (code "83") (name "/PIN32") (class "Default")
      (node (ref "U1") (pin "32") (pinfunction "PD10_32") (pintype "passive"))
      (node (ref "XIO") (pin "13") (pinfunction "13_13") (pintype "passive"))
    )
    (net (code "84") (name "/PIN33") (class "Default")
      (node (ref "U1") (pin "55") (pinfunction "PC1_55") (pintype "passive"))
      (node (ref "XIO") (pin "14") (pinfunction "14_14") (pintype "passive"))
    )
    (net (code "85") (name "/PIN34") (class "Default")
      (node (ref "U1") (pin "59") (pinfunction "PC2_59") (pintype "passive"))
      (node (ref "XIO") (pin "15") (pinfunction "15_15") (pintype "passive"))
    )
    (net (code "86") (name "/PIN35") (class "Default")
      (node (ref "U1") (pin "60") (pinfunction "PC3_60") (pintype "passive"))
      (node (ref "XIO") (pin "16") (pinfunction "16_16") (pintype "passive"))
    )
    (net (code "87") (name "/PIN36") (class "Default")
      (node (ref "U1") (pin "116") (pinfunction "PC4_116") (pintype "passive"))
      (node (ref "XIO") (pin "17") (pinfunction "17_17") (pintype "passive"))
    )
    (net (code "88") (name "/PIN37") (class "Default")
      (node (ref "U1") (pin "63") (pinfunction "PC5_63") (pintype "passive"))
      (node (ref "XIO") (pin "18") (pinfunction "18_18") (pintype "passive"))
    )
    (net (code "89") (name "/PIN38") (class "Default")
      (node (ref "U1") (pin "64") (pinfunction "PC6_64") (pintype "passive"))
      (node (ref "XIO") (pin "19") (pinfunction "19_19") (pintype "passive"))
    )
    (net (code "90") (name "/PIN39") (class "Default")
      (node (ref "U1") (pin "65") (pinfunction "PC7_65") (pintype "passive"))
      (node (ref "XIO") (pin "20") (pinfunction "20_20") (pintype "passive"))
    )
    (net (code "91") (name "/PIN40") (class "Default")
      (node (ref "U1") (pin "66") (pinfunction "PC8_66") (pintype "passive"))
      (node (ref "XIO") (pin "21") (pinfunction "21_21") (pintype "passive"))
    )
    (net (code "92") (name "/PIN41") (class "Default")
      (node (ref "U1") (pin "67") (pinfunction "PC9_67") (pintype "passive"))
      (node (ref "XIO") (pin "22") (pinfunction "22_22") (pintype "passive"))
    )
    (net (code "93") (name "/PIN42") (class "Default")
      (node (ref "U1") (pin "71") (pinfunction "PA19_71") (pintype "passive"))
      (node (ref "XIO") (pin "23") (pinfunction "23_23") (pintype "passive"))
    )
    (net (code "94") (name "/PIN43") (class "Default")
      (node (ref "U1") (pin "72") (pinfunction "PA20_72") (pintype "passive"))
      (node (ref "XIO") (pin "24") (pinfunction "24_24") (pintype "passive"))
    )
    (net (code "95") (name "/PIN44") (class "Default")
      (node (ref "U1") (pin "101") (pinfunction "PC19_101") (pintype "passive"))
      (node (ref "XIO") (pin "25") (pinfunction "25_25") (pintype "passive"))
    )
    (net (code "96") (name "/PIN45") (class "Default")
      (node (ref "U1") (pin "100") (pinfunction "PC18_100") (pintype "passive"))
      (node (ref "XIO") (pin "26") (pinfunction "26_26") (pintype "passive"))
    )
    (net (code "97") (name "/PIN46") (class "Default")
      (node (ref "U1") (pin "99") (pinfunction "PC17_99") (pintype "passive"))
      (node (ref "XIO") (pin "27") (pinfunction "27_27") (pintype "passive"))
    )
    (net (code "98") (name "/PIN47") (class "Default")
      (node (ref "U1") (pin "98") (pinfunction "PC16_98") (pintype "passive"))
      (node (ref "XIO") (pin "28") (pinfunction "28_28") (pintype "passive"))
    )
    (net (code "99") (name "/PIN48") (class "Default")
      (node (ref "U1") (pin "97") (pinfunction "PC15_97") (pintype "passive"))
      (node (ref "XIO") (pin "29") (pinfunction "29_29") (pintype "passive"))
    )
    (net (code "100") (name "/PIN49") (class "Default")
      (node (ref "U1") (pin "96") (pinfunction "PC14_96") (pintype "passive"))
      (node (ref "XIO") (pin "30") (pinfunction "30_30") (pintype "passive"))
    )
    (net (code "101") (name "/PIN50") (class "Default")
      (node (ref "U1") (pin "95") (pinfunction "PC13_95") (pintype "passive"))
      (node (ref "XIO") (pin "31") (pinfunction "31_31") (pintype "passive"))
    )
    (net (code "102") (name "/PIN51") (class "Default")
      (node (ref "U1") (pin "94") (pinfunction "PC12_94") (pintype "passive"))
      (node (ref "XIO") (pin "32") (pinfunction "32_32") (pintype "passive"))
    )
    (net (code "103") (name "/PWM2") (class "Default")
      (node (ref "PWML") (pin "3") (pinfunction "3_3") (pintype "passive"))
      (node (ref "U1") (pin "144") (pinfunction "PB25_144") (pintype "passive"))
    )
    (net (code "104") (name "/PWM3") (class "Default")
      (node (ref "PWML") (pin "4") (pinfunction "4_4") (pintype "passive"))
      (node (ref "U1") (pin "139") (pinfunction "PC28_139") (pintype "passive"))
    )
    (net (code "105") (name "/PWM5") (class "Default")
      (node (ref "PWML") (pin "6") (pinfunction "6_6") (pintype "passive"))
      (node (ref "U1") (pin "136") (pinfunction "PC25_136") (pintype "passive"))
    )
    (net (code "106") (name "/PWM6") (class "Default")
      (node (ref "PWML") (pin "7") (pinfunction "7_7") (pintype "passive"))
      (node (ref "U1") (pin "135") (pinfunction "PC24_135") (pintype "passive"))
    )
    (net (code "107") (name "/PWM7") (class "Default")
      (node (ref "PWML") (pin "8") (pinfunction "8_8") (pintype "passive"))
      (node (ref "U1") (pin "134") (pinfunction "PC23_134") (pintype "passive"))
    )
    (net (code "108") (name "/PWM8") (class "Default")
      (node (ref "PWMH") (pin "1") (pinfunction "1_1") (pintype "passive"))
      (node (ref "U1") (pin "133") (pinfunction "PC22_133") (pintype "passive"))
    )
    (net (code "109") (name "/PWM9") (class "Default")
      (node (ref "PWMH") (pin "2") (pinfunction "2_2") (pintype "passive"))
      (node (ref "U1") (pin "132") (pinfunction "PC21_132") (pintype "passive"))
    )
    (net (code "110") (name "/PWM11") (class "Default")
      (node (ref "PWMH") (pin "4") (pinfunction "4_4") (pintype "passive"))
      (node (ref "U1") (pin "20") (pinfunction "PD7_20") (pintype "passive"))
    )
    (net (code "111") (name "/PWM12") (class "Default")
      (node (ref "PWMH") (pin "5") (pinfunction "5_5") (pintype "passive"))
      (node (ref "U1") (pin "21") (pinfunction "PD8_21") (pintype "passive"))
    )
    (net (code "112") (name "/PWM13") (class "Default")
      (node (ref "IC1") (pin "3") (pinfunction "+IN_3") (pintype "passive"))
      (node (ref "PWMH") (pin "6") (pinfunction "6_6") (pintype "passive"))
      (node (ref "U1") (pin "68") (pinfunction "PB27_68") (pintype "passive"))
    )
    (net (code "113") (name "/RD+") (class "Default")
      (node (ref "IC6") (pin "29") (pinfunction "D+_29") (pintype "passive"))
      (node (ref "R20") (pin "1") (pinfunction "1_1") (pintype "passive"))
    )
    (net (code "114") (name "/RD-") (class "Default")
      (node (ref "IC6") (pin "30") (pinfunction "D-_30") (pintype "passive"))
      (node (ref "R19") (pin "1") (pinfunction "1_1") (pintype "passive"))
    )
    (net (code "115") (name "/RESET2") (class "Default")
      (node (ref "D2") (pin "A") (pinfunction "A_A") (pintype "passive"))
      (node (ref "IC6") (pin "24") (pinfunction "RESET(PC1/DW)_24") (pintype "passive"))
      (node (ref "ICSP1") (pin "5") (pinfunction "5_5") (pintype "passive"))
      (node (ref "R13") (pin "1") (pinfunction "1_1") (pintype "passive"))
    )
    (net (code "116") (name "/RESETA") (class "Default")
      (node (ref "MACB") (pin "2") (pinfunction "2_2") (pintype "passive+no_connect"))
    )
    (net (code "117") (name "/RESET_CMD") (class "Default")
      (node (ref "IC6") (pin "22") (pinfunction "(INT4/ICP1/CLK0)PC7_22") (pintype "passive"))
      (node (ref "R23") (pin "1") (pinfunction "1_1") (pintype "passive"))
    )
    (net (code "118") (name "/RX") (class "Default")
      (node (ref "IC10") (pin "4") (pinfunction "O_4") (pintype "passive"))
      (node (ref "PWML") (pin "1") (pinfunction "1_1") (pintype "passive"))
      (node (ref "U1") (pin "27") (pinfunction "PA8_27") (pintype "passive"))
    )
    (net (code "119") (name "/RXD0") (class "Default")
      (node (ref "COMMUNICATION") (pin "2") (pinfunction "2_2") (pintype "passive"))
      (node (ref "U1") (pin "18") (pinfunction "PD5_18") (pintype "passive"))
    )
    (net (code "120") (name "/RXD1") (class "Default")
      (node (ref "COMMUNICATION") (pin "4") (pinfunction "4_4") (pintype "passive"))
      (node (ref "U1") (pin "5") (pinfunction "PA12_5") (pintype "passive"))
    )
    (net (code "121") (name "/RXD2") (class "Default")
      (node (ref "COMMUNICATION") (pin "6") (pinfunction "6_6") (pintype "passive"))
      (node (ref "U1") (pin "3") (pinfunction "PA10_3") (pintype "passive"))
    )
    (net (code "122") (name "/RXL") (class "Default")
      (node (ref "RX") (pin "C") (pinfunction "C_C") (pintype "passive"))
      (node (ref "U1") (pin "103") (pinfunction "PC30_103") (pintype "passive"))
    )
    (net (code "123") (name "/RXL-U2") (class "Default")
      (node (ref "IC6") (pin "10") (pinfunction "(INT5/AIN3)PD4_10") (pintype "passive"))
      (node (ref "RX1") (pin "C") (pinfunction "C_C") (pintype "passive"))
    )
    (net (code "124") (name "/SCK2") (class "Default")
      (node (ref "IC6") (pin "15") (pinfunction "(SCLK/PCINT1)PB1_15") (pintype "passive"))
      (node (ref "ICSP1") (pin "3") (pinfunction "3_3") (pintype "passive"))
    )
    (net (code "125") (name "/SCL0-3") (class "Default")
      (node (ref "COMMUNICATION") (pin "8") (pinfunction "8_8") (pintype "passive"))
      (node (ref "RN5") (pin "7") (pinfunction "2_7") (pintype "passive"))
      (node (ref "U1") (pin "87") (pinfunction "PB13_87") (pintype "passive"))
    )
    (net (code "126") (name "/SCL1") (class "Default")
      (node (ref "PWMH") (pin "10") (pinfunction "10_10") (pintype "passive"))
      (node (ref "U1") (pin "70") (pinfunction "PA18_70") (pintype "passive"))
    )
    (net (code "127") (name "/SDA0-3") (class "Default")
      (node (ref "COMMUNICATION") (pin "7") (pinfunction "7_7") (pintype "passive"))
      (node (ref "RN5") (pin "8") (pinfunction "2_8") (pintype "passive"))
      (node (ref "U1") (pin "86") (pinfunction "PB12_86") (pintype "passive"))
    )
    (net (code "128") (name "/SDA1") (class "Default")
      (node (ref "PWMH") (pin "9") (pinfunction "9_9") (pintype "passive"))
      (node (ref "U1") (pin "9") (pinfunction "PA17_9") (pintype "passive"))
    )
    (net (code "129") (name "/SPCK") (class "Default")
      (node (ref "SPI") (pin "3") (pinfunction "3_3") (pintype "passive"))
      (node (ref "U1") (pin "110") (pinfunction "PA27_110") (pintype "passive"))
    )
    (net (code "130") (name "/SS0{slash}PWM10") (class "Default")
      (node (ref "PWMH") (pin "3") (pinfunction "3_3") (pintype "passive"))
      (node (ref "U1") (pin "102") (pinfunction "PC29_102") (pintype "passive"))
      (node (ref "U1") (pin "111") (pinfunction "PA28_111") (pintype "passive"))
    )
    (net (code "131") (name "/SS1{slash}PWM4") (class "Default")
      (node (ref "PWML") (pin "5") (pinfunction "5_5") (pintype "passive"))
      (node (ref "U1") (pin "112") (pinfunction "PA29_112") (pintype "passive"))
      (node (ref "U1") (pin "137") (pinfunction "PC26_137") (pintype "passive"))
    )
    (net (code "132") (name "/SS3") (class "Default")
      (node (ref "U1") (pin "142") (pinfunction "PB23_142") (pintype "passive"))
    )
    (net (code "133") (name "/SW") (class "Default")
      (node (ref "C42") (pin "2") (pinfunction "2_2") (pintype "passive"))
      (node (ref "D4") (pin "P$1") (pinfunction "K_P$1") (pintype "passive"))
      (node (ref "IC2") (pin "6") (pinfunction "SW_6") (pintype "passive"))
      (node (ref "L4") (pin "P$1") (pinfunction "1_P$1") (pintype "passive"))
    )
    (net (code "134") (name "/TX") (class "Default")
      (node (ref "IC6") (pin "8") (pinfunction "(RXD1/AIN1/INT2)PD2_8") (pintype "passive"))
      (node (ref "PWML") (pin "2") (pinfunction "2_2") (pintype "passive"))
      (node (ref "U1") (pin "2") (pinfunction "PA9_2") (pintype "passive"))
    )
    (net (code "135") (name "/TXD0") (class "Default")
      (node (ref "COMMUNICATION") (pin "1") (pinfunction "1_1") (pintype "passive"))
      (node (ref "U1") (pin "17") (pinfunction "PD4_17") (pintype "passive"))
    )
    (net (code "136") (name "/TXD1") (class "Default")
      (node (ref "COMMUNICATION") (pin "3") (pinfunction "3_3") (pintype "passive"))
      (node (ref "U1") (pin "6") (pinfunction "PA13_6") (pintype "passive"))
    )
    (net (code "137") (name "/TXD2") (class "Default")
      (node (ref "COMMUNICATION") (pin "5") (pinfunction "5_5") (pintype "passive"))
      (node (ref "U1") (pin "4") (pinfunction "PA11_4") (pintype "passive"))
    )
    (net (code "138") (name "/TXL") (class "Default")
      (node (ref "TX") (pin "C") (pinfunction "C_C") (pintype "passive"))
      (node (ref "U1") (pin "107") (pinfunction "PA21_107") (pintype "passive"))
    )
    (net (code "139") (name "/TXL-U2") (class "Default")
      (node (ref "IC6") (pin "11") (pinfunction "(XCK/AIN4/PCINT12)PD5_11") (pintype "passive"))
      (node (ref "TX1") (pin "C") (pinfunction "C_C") (pintype "passive"))
    )
    (net (code "140") (name "/UOTGID") (class "Default")
      (node (ref "U1") (pin "129") (pinfunction "PB11_129") (pintype "passive"))
      (node (ref "USB1") (pin "4") (pinfunction "ID_4") (pintype "passive"))
      (node (ref "Z5") (pin "2") (pinfunction "2_2") (pintype "passive"))
    )
    (net (code "141") (name "/UOTGVBOF") (class "Default")
      (node (ref "R3") (pin "1") (pinfunction "1_1") (pintype "passive"))
      (node (ref "U1") (pin "128") (pinfunction "PB10_128") (pintype "passive"))
    )
    (net (code "142") (name "/USBVCC") (class "Default")
      (node (ref "C27") (pin "+") (pinfunction "+_+") (pintype "passive"))
      (node (ref "C35") (pin "+") (pinfunction "+_+") (pintype "passive"))
      (node (ref "F1") (pin "1") (pinfunction "1_1") (pintype "passive"))
      (node (ref "R2") (pin "2") (pinfunction "2_2") (pintype "passive"))
      (node (ref "R21") (pin "2") (pinfunction "2_2") (pintype "passive"))
      (node (ref "T1") (pin "1") (pinfunction "D_1") (pintype "passive"))
    )
    (net (code "143") (name "/USBVCCU2") (class "Default")
      (node (ref "C28") (pin "1") (pinfunction "1_1") (pintype "passive"))
      (node (ref "F2") (pin "1") (pinfunction "1_1") (pintype "passive"))
      (node (ref "IC6") (pin "31") (pinfunction "UVCC_31") (pintype "passive"))
      (node (ref "T2") (pin "1") (pinfunction "D_1") (pintype "passive"))
    )
    (net (code "144") (name "/VBG") (class "Default")
      (node (ref "C25") (pin "1") (pinfunction "1_1") (pintype "passive"))
      (node (ref "R7") (pin "2") (pinfunction "2_2") (pintype "passive"))
      (node (ref "U1") (pin "40") (pinfunction "VBG_40") (pintype "passive"))
    )
    (net (code "145") (name "/VDDANA") (class "Default")
      (node (ref "C10") (pin "2") (pinfunction "2_2") (pintype "passive"))
      (node (ref "C3") (pin "+") (pinfunction "+_+") (pintype "passive"))
      (node (ref "L1") (pin "2") (pinfunction "2_2") (pintype "passive"))
      (node (ref "U1") (pin "73") (pinfunction "VDDANA_73") (pintype "passive"))
    )
    (net (code "146") (name "/VDDOUT") (class "Default")
      (node (ref "C11") (pin "+") (pinfunction "+_+") (pintype "passive"))
      (node (ref "C12") (pin "2") (pinfunction "2_2") (pintype "passive"))
      (node (ref "C13") (pin "2") (pinfunction "2_2") (pintype "passive"))
      (node (ref "C14") (pin "2") (pinfunction "2_2") (pintype "passive"))
      (node (ref "C15") (pin "2") (pinfunction "2_2") (pintype "passive"))
      (node (ref "C16") (pin "2") (pinfunction "2_2") (pintype "passive"))
      (node (ref "C17") (pin "2") (pinfunction "2_2") (pintype "passive"))
      (node (ref "L5") (pin "1") (pinfunction "1_1") (pintype "passive"))
      (node (ref "U1") (pin "10") (pinfunction "VDDCORE1_10") (pintype "passive"))
      (node (ref "U1") (pin "104") (pinfunction "VDDCORE4_104") (pintype "passive"))
      (node (ref "U1") (pin "124") (pinfunction "VDDCORE5_124") (pintype "passive"))
      (node (ref "U1") (pin "45") (pinfunction "VDDCORE2_45") (pintype "passive"))
      (node (ref "U1") (pin "56") (pinfunction "VDDOUT_56") (pintype "passive"))
      (node (ref "U1") (pin "61") (pinfunction "VDDCORE3_61") (pintype "passive"))
    )
    (net (code "147") (name "/VDDOUTMI") (class "Default")
      (node (ref "C2") (pin "+") (pinfunction "+_+") (pintype "passive"))
      (node (ref "C9") (pin "2") (pinfunction "2_2") (pintype "passive"))
      (node (ref "L2") (pin "2") (pinfunction "2_2") (pintype "passive"))
      (node (ref "U1") (pin "41") (pinfunction "VDDUTMI_41") (pintype "passive"))
    )
    (net (code "148") (name "/VDDPLL") (class "Default")
      (node (ref "C32") (pin "2") (pinfunction "2_2") (pintype "passive"))
      (node (ref "C33") (pin "+") (pinfunction "+_+") (pintype "passive"))
      (node (ref "L5") (pin "2") (pinfunction "2_2") (pintype "passive"))
      (node (ref "U1") (pin "34") (pinfunction "VDDPLL_34") (pintype "passive"))
    )
    (net (code "149") (name "/VIN") (class "Default")
      (node (ref "C41") (pin "+") (pinfunction "+_+") (pintype "passive"))
      (node (ref "IC2") (pin "5") (pinfunction "VIN_5") (pintype "passive"))
      (node (ref "L6") (pin "1") (pinfunction "1_1") (pintype "passive"))
      (node (ref "PC1") (pin "+") (pinfunction "+_+") (pintype "passive"))
      (node (ref "POWER") (pin "8") (pinfunction "8_8") (pintype "passive"))
      (node (ref "R10") (pin "1") (pinfunction "1_1") (pintype "passive"))
      (node (ref "RN4") (pin "6") (pinfunction "2_6") (pintype "passive"))
    )
    (net (code "150") (name "/VIN+") (class "Default")
      (node (ref "D1") (pin "C") (pinfunction "C_C") (pintype "passive"))
      (node (ref "L6") (pin "2") (pinfunction "2_2") (pintype "passive"))
      (node (ref "X2") (pin "2") (pinfunction "2_2") (pintype "passive"))
    )
    (net (code "151") (name "/VUCAP") (class "Default")
      (node (ref "C38") (pin "1") (pinfunction "1_1") (pintype "passive"))
      (node (ref "IC6") (pin "27") (pinfunction "UCAP_27") (pintype "passive"))
    )
    (net (code "152") (name "/XIN") (class "Default")
      (node (ref "C22") (pin "1") (pinfunction "1_1") (pintype "passive"))
      (node (ref "U1") (pin "36") (pinfunction "XIN_36") (pintype "passive"))
      (node (ref "Y1") (pin "1") (pinfunction "C1_1") (pintype "passive"))
    )
    (net (code "153") (name "/XIN32") (class "Default")
      (node (ref "C24") (pin "1") (pinfunction "1_1") (pintype "passive"))
      (node (ref "U1") (pin "48") (pinfunction "XIN32_48") (pintype "passive"))
      (node (ref "Y2") (pin "P$2") (pinfunction "2_P$2") (pintype "passive"))
    )
    (net (code "154") (name "/XOUT") (class "Default")
      (node (ref "C21") (pin "1") (pinfunction "1_1") (pintype "passive"))
      (node (ref "U1") (pin "35") (pinfunction "XOUT_35") (pintype "passive"))
      (node (ref "Y1") (pin "3") (pinfunction "C2_3") (pintype "passive"))
    )
    (net (code "155") (name "/XOUT32") (class "Default")
      (node (ref "C23") (pin "1") (pinfunction "1_1") (pintype "passive"))
      (node (ref "U1") (pin "49") (pinfunction "XOUT32_49") (pintype "passive"))
      (node (ref "Y2") (pin "P$1") (pinfunction "1_P$1") (pintype "passive"))
    )
    (net (code "156") (name "/XT1") (class "Default")
      (node (ref "C39") (pin "1") (pinfunction "1_1") (pintype "passive"))
      (node (ref "IC6") (pin "1") (pinfunction "XTAL1_1") (pintype "passive"))
      (node (ref "R9") (pin "1") (pinfunction "1_1") (pintype "passive"))
      (node (ref "Y4") (pin "1") (pinfunction "C1_1") (pintype "passive"))
    )
    (net (code "157") (name "/XT2") (class "Default")
      (node (ref "C40") (pin "1") (pinfunction "1_1") (pintype "passive"))
      (node (ref "IC6") (pin "2") (pinfunction "XTAL2(PC0)_2") (pintype "passive"))
      (node (ref "R9") (pin "2") (pinfunction "2_2") (pintype "passive"))
      (node (ref "Y4") (pin "3") (pinfunction "C2_3") (pintype "passive"))
    )
    (net (code "158") (name "/XUSB") (class "Default")
      (node (ref "C26") (pin "1") (pinfunction "1_1") (pintype "passive"))
      (node (ref "F1") (pin "2") (pinfunction "2_2") (pintype "passive"))
      (node (ref "U1") (pin "39") (pinfunction "VBUS_39") (pintype "passive"))
      (node (ref "USB1") (pin "1") (pinfunction "VUSB_1") (pintype "passive"))
    )
    (net (code "159") (name "/XVCC") (class "Default")
      (node (ref "F2") (pin "2") (pinfunction "2_2") (pintype "passive"))
      (node (ref "J3") (pin "P1") (pinfunction "VBUS_P1") (pintype "passive"))
    )
    (net (code "160") (name "GND") (class "Default")
      (node (ref "C1") (pin "-") (pinfunction "-_-") (pintype "passive"))
      (node (ref "C10") (pin "1") (pinfunction "1_1") (pintype "passive"))
      (node (ref "C11") (pin "-") (pinfunction "-_-") (pintype "passive"))
      (node (ref "C12") (pin "1") (pinfunction "1_1") (pintype "passive"))
      (node (ref "C13") (pin "1") (pinfunction "1_1") (pintype "passive"))
      (node (ref "C14") (pin "1") (pinfunction "1_1") (pintype "passive"))
      (node (ref "C15") (pin "1") (pinfunction "1_1") (pintype "passive"))
      (node (ref "C16") (pin "1") (pinfunction "1_1") (pintype "passive"))
      (node (ref "C17") (pin "1") (pinfunction "1_1") (pintype "passive"))
      (node (ref "C18") (pin "1") (pinfunction "1_1") (pintype "passive"))
      (node (ref "C19") (pin "1") (pinfunction "1_1") (pintype "passive"))
      (node (ref "C2") (pin "-") (pinfunction "-_-") (pintype "passive"))
      (node (ref "C21") (pin "2") (pinfunction "2_2") (pintype "passive"))
      (node (ref "C22") (pin "2") (pinfunction "2_2") (pintype "passive"))
      (node (ref "C23") (pin "2") (pinfunction "2_2") (pintype "passive"))
      (node (ref "C24") (pin "2") (pinfunction "2_2") (pintype "passive"))
      (node (ref "C25") (pin "2") (pinfunction "2_2") (pintype "passive"))
      (node (ref "C26") (pin "2") (pinfunction "2_2") (pintype "passive"))
      (node (ref "C27") (pin "-") (pinfunction "-_-") (pintype "passive"))
      (node (ref "C28") (pin "2") (pinfunction "2_2") (pintype "passive"))
      (node (ref "C29") (pin "-") (pinfunction "-_-") (pintype "passive"))
      (node (ref "C3") (pin "-") (pinfunction "-_-") (pintype "passive"))
      (node (ref "C30") (pin "1") (pinfunction "1_1") (pintype "passive"))
      (node (ref "C31") (pin "1") (pinfunction "1_1") (pintype "passive"))
      (node (ref "C32") (pin "1") (pinfunction "1_1") (pintype "passive"))
      (node (ref "C33") (pin "-") (pinfunction "-_-") (pintype "passive"))
      (node (ref "C34") (pin "1") (pinfunction "1_1") (pintype "passive"))
      (node (ref "C35") (pin "-") (pinfunction "-_-") (pintype "passive"))
      (node (ref "C36") (pin "2") (pinfunction "2_2") (pintype "passive"))
      (node (ref "C37") (pin "2") (pinfunction "2_2") (pintype "passive"))
      (node (ref "C38") (pin "2") (pinfunction "2_2") (pintype "passive"))
      (node (ref "C39") (pin "2") (pinfunction "2_2") (pintype "passive"))
      (node (ref "C4") (pin "1") (pinfunction "1_1") (pintype "passive"))
      (node (ref "C40") (pin "2") (pinfunction "2_2") (pintype "passive"))
      (node (ref "C41") (pin "-") (pinfunction "-_-") (pintype "passive"))
      (node (ref "C5") (pin "1") (pinfunction "1_1") (pintype "passive"))
      (node (ref "C6") (pin "1") (pinfunction "1_1") (pintype "passive"))
      (node (ref "C7") (pin "1") (pinfunction "1_1") (pintype "passive"))
      (node (ref "C8") (pin "1") (pinfunction "1_1") (pintype "passive"))
      (node (ref "C9") (pin "1") (pinfunction "1_1") (pintype "passive"))
      (node (ref "D1") (pin "A") (pinfunction "A_A") (pintype "passive"))
      (node (ref "D4") (pin "P$2") (pinfunction "A_P$2") (pintype "passive"))
      (node (ref "DEBUG") (pin "1") (pinfunction "1_1") (pintype "passive"))
      (node (ref "IC1") (pin "4") (pinfunction "V-_4") (pintype "passive"))
      (node (ref "IC10") (pin "1") (pinfunction "OE_1") (pintype "passive"))
      (node (ref "IC10") (pin "3") (pinfunction "GND_3") (pintype "passive"))
      (node (ref "IC2") (pin "2") (pinfunction "GND_2") (pintype "passive"))
      (node (ref "IC4") (pin "1") (pinfunction "GND/ADJ_1") (pintype "passive"))
      (node (ref "IC6") (pin "28") (pinfunction "UGND_28") (pintype "passive"))
      (node (ref "IC6") (pin "3") (pinfunction "GND_3") (pintype "passive"))
      (node (ref "IC6") (pin "33") (pinfunction "PAD_33") (pintype "passive"))
      (node (ref "ICSP1") (pin "6") (pinfunction "6_6") (pintype "passive"))
      (node (ref "J3") (pin "P$1") (pinfunction "SH7_P$1") (pintype "passive"))
      (node (ref "J3") (pin "P$2") (pinfunction "SH8_P$2") (pintype "passive"))
      (node (ref "J3") (pin "P$3") (pinfunction "SH9_P$3") (pintype "passive"))
      (node (ref "J3") (pin "P$4") (pinfunction "SH10_P$4") (pintype "passive"))
      (node (ref "J3") (pin "P$5") (pinfunction "SH11_P$5") (pintype "passive"))
      (node (ref "J3") (pin "P$6") (pinfunction "SH12_P$6") (pintype "passive"))
      (node (ref "J3") (pin "P$7") (pinfunction "SH13_P$7") (pintype "passive"))
      (node (ref "J3") (pin "P$8") (pinfunction "SH14_P$8") (pintype "passive"))
      (node (ref "J3") (pin "P5") (pinfunction "GND_P5") (pintype "passive"))
      (node (ref "J3") (pin "S1") (pinfunction "SH1_S1") (pintype "passive"))
      (node (ref "J3") (pin "S2") (pinfunction "SH2_S2") (pintype "passive"))
      (node (ref "J3") (pin "S3") (pinfunction "SH3_S3") (pintype "passive"))
      (node (ref "J3") (pin "S4") (pinfunction "SH4_S4") (pintype "passive"))
      (node (ref "J3") (pin "S5") (pinfunction "SH5_S5") (pintype "passive"))
      (node (ref "J3") (pin "S6") (pinfunction "SH6_S6") (pintype "passive"))
      (node (ref "JTAG") (pin "3") (pinfunction "3_3") (pintype "passive"))
      (node (ref "JTAG") (pin "5") (pinfunction "5_5") (pintype "passive"))
      (node (ref "JTAG") (pin "9") (pinfunction "9_9") (pintype "passive"))
      (node (ref "L") (pin "C") (pinfunction "C_C") (pintype "passive"))
      (node (ref "ON") (pin "C") (pinfunction "C_C") (pintype "passive"))
      (node (ref "PC1") (pin "-") (pinfunction "-_-") (pintype "passive"))
      (node (ref "PC2") (pin "-") (pinfunction "-_-") (pintype "passive"))
      (node (ref "POWER") (pin "6") (pinfunction "6_6") (pintype "passive"))
      (node (ref "POWER") (pin "7") (pinfunction "7_7") (pintype "passive"))
      (node (ref "PWMH") (pin "7") (pinfunction "7_7") (pintype "passive"))
      (node (ref "Q2") (pin "2") (pinfunction "E_2") (pintype "passive"))
      (node (ref "R11") (pin "2") (pinfunction "2_2") (pintype "passive"))
      (node (ref "R18") (pin "2") (pinfunction "2_2") (pintype "passive"))
      (node (ref "R2") (pin "1") (pinfunction "1_1") (pintype "passive"))
      (node (ref "R7") (pin "1") (pinfunction "1_1") (pintype "passive"))
      (node (ref "R8") (pin "1") (pinfunction "1_1") (pintype "passive"))
      (node (ref "RESET") (pin "1") (pinfunction "1_1") (pintype "passive"))
      (node (ref "RESET") (pin "2") (pinfunction "2_2") (pintype "passive"))
      (node (ref "RN1") (pin "1") (pinfunction "1_1") (pintype "passive"))
      (node (ref "RN1") (pin "2") (pinfunction "1_2") (pintype "passive"))
      (node (ref "RN1") (pin "7") (pinfunction "2_7") (pintype "passive"))
      (node (ref "RN1") (pin "8") (pinfunction "2_8") (pintype "passive"))
      (node (ref "RN2") (pin "1") (pinfunction "1_1") (pintype "passive"))
      (node (ref "RN2") (pin "4") (pinfunction "1_4") (pintype "passive"))
      (node (ref "RN2") (pin "5") (pinfunction "2_5") (pintype "passive"))
      (node (ref "RN2") (pin "8") (pinfunction "2_8") (pintype "passive"))
      (node (ref "RN4") (pin "1") (pinfunction "1_1") (pintype "passive"))
      (node (ref "RN4") (pin "2") (pinfunction "1_2") (pintype "passive"))
      (node (ref "RN4") (pin "5") (pinfunction "2_5") (pintype "passive"))
      (node (ref "RN4") (pin "7") (pinfunction "2_7") (pintype "passive"))
      (node (ref "SPI") (pin "6") (pinfunction "6_6") (pintype "passive"))
      (node (ref "T2") (pin "3") (pinfunction "G_3") (pintype "passive"))
      (node (ref "U1") (pin "106") (pinfunction "GND3_106") (pintype "passive"))
      (node (ref "U1") (pin "12") (pinfunction "GND1_12") (pintype "passive"))
      (node (ref "U1") (pin "126") (pinfunction "GND4_126") (pintype "passive"))
      (node (ref "U1") (pin "33") (pinfunction "GNDPLL_33") (pintype "passive"))
      (node (ref "U1") (pin "44") (pinfunction "GNDUTMI_44") (pintype "passive"))
      (node (ref "U1") (pin "46") (pinfunction "JTAGSEL_46") (pintype "passive"))
      (node (ref "U1") (pin "54") (pinfunction "GNDBU_54") (pintype "passive"))
      (node (ref "U1") (pin "58") (pinfunction "GND2_58") (pintype "passive"))
      (node (ref "U1") (pin "74") (pinfunction "GNDANA_74") (pintype "passive"))
      (node (ref "USB1") (pin "5") (pinfunction "UGND_5") (pintype "passive"))
      (node (ref "USB1") (pin "P$1") (pinfunction "G1_P$1") (pintype "passive"))
      (node (ref "USB1") (pin "P$10") (pinfunction "G10_P$10") (pintype "passive"))
      (node (ref "USB1") (pin "P$11") (pinfunction "G11_P$11") (pintype "passive"))
      (node (ref "USB1") (pin "P$2") (pinfunction "G2_P$2") (pintype "passive"))
      (node (ref "USB1") (pin "P$3") (pinfunction "G3_P$3") (pintype "passive"))
      (node (ref "USB1") (pin "P$4") (pinfunction "G4_P$4") (pintype "passive"))
      (node (ref "USB1") (pin "P$5") (pinfunction "G5_P$5") (pintype "passive"))
      (node (ref "USB1") (pin "P$6") (pinfunction "G6_P$6") (pintype "passive"))
      (node (ref "USB1") (pin "P$7") (pinfunction "G7_P$7") (pintype "passive"))
      (node (ref "USB1") (pin "P$8") (pinfunction "G8_P$8") (pintype "passive"))
      (node (ref "USB1") (pin "P$9") (pinfunction "G9_P$9") (pintype "passive"))
      (node (ref "USB1") (pin "S1") (pinfunction "SH1_S1") (pintype "passive"))
      (node (ref "USB1") (pin "S2") (pinfunction "SH2_S2") (pintype "passive"))
      (node (ref "USB1") (pin "S3") (pinfunction "SH3_S3") (pintype "passive"))
      (node (ref "USB1") (pin "S4") (pinfunction "SH4_S4") (pintype "passive"))
      (node (ref "X2") (pin "1") (pinfunction "1_1") (pintype "passive"))
      (node (ref "X2") (pin "3") (pinfunction "3_3") (pintype "passive"))
      (node (ref "XIO") (pin "35") (pinfunction "35_35") (pintype "passive"))
      (node (ref "XIO") (pin "36") (pinfunction "36_36") (pintype "passive"))
      (node (ref "Y1") (pin "2") (pinfunction "GND@1_2") (pintype "passive"))
      (node (ref "Y1") (pin "4") (pinfunction "GND@2_4") (pintype "passive"))
      (node (ref "Y4") (pin "2") (pinfunction "GND@1_2") (pintype "passive"))
      (node (ref "Y4") (pin "4") (pinfunction "GND@2_4") (pintype "passive"))
      (node (ref "Z1") (pin "2") (pinfunction "2_2") (pintype "passive"))
      (node (ref "Z2") (pin "2") (pinfunction "2_2") (pintype "passive"))
      (node (ref "Z3") (pin "1") (pinfunction "1_1") (pintype "passive"))
      (node (ref "Z4") (pin "1") (pinfunction "1_1") (pintype "passive"))
      (node (ref "Z5") (pin "1") (pinfunction "1_1") (pintype "passive"))
    )
    (net (code "161") (name "Net-(BR1-C)") (class "Default")
      (node (ref "BR1") (pin "2") (pinfunction "C_2") (pintype "passive"))
      (node (ref "C34") (pin "2") (pinfunction "2_2") (pintype "passive"))
      (node (ref "JR1") (pin "2") (pinfunction "2_2") (pintype "passive"))
      (node (ref "L3") (pin "1") (pinfunction "1_1") (pintype "passive"))
    )
    (net (code "162") (name "Net-(IC6-(CTS{slash}HWB{slash}AIN6{slash}TO{slash}INT7)PD7)") (class "Default")
      (node (ref "IC6") (pin "13") (pinfunction "(CTS/HWB/AIN6/TO/INT7)PD7_13") (pintype "passive"))
      (node (ref "R18") (pin "1") (pinfunction "1_1") (pintype "passive"))
    )
    (net (code "163") (name "Net-(POWER-Pad1)") (class "Default")
      (node (ref "POWER") (pin "1") (pinfunction "1_1") (pintype "passive"))
    )
    (net (code "164") (name "Net-(Q2-B)") (class "Default")
      (node (ref "Q2") (pin "1") (pinfunction "B_1") (pintype "passive"))
      (node (ref "R3") (pin "2") (pinfunction "2_2") (pintype "passive"))
      (node (ref "RN4") (pin "8") (pinfunction "2_8") (pintype "passive"))
    )
    (net (code "165") (name "Net-(R14-Pad2)") (class "Default")
      (node (ref "R14") (pin "2") (pinfunction "2_2") (pintype "passive"))
      (node (ref "TX1") (pin "A") (pinfunction "A_A") (pintype "passive"))
    )
    (net (code "166") (name "Net-(R15-Pad2)") (class "Default")
      (node (ref "R15") (pin "2") (pinfunction "2_2") (pintype "passive"))
      (node (ref "RX1") (pin "A") (pinfunction "A_A") (pintype "passive"))
    )
    (net (code "167") (name "Net-(RN3-Pad1)") (class "Default")
      (node (ref "RN3") (pin "1") (pinfunction "1_1") (pintype "passive"))
      (node (ref "RX") (pin "A") (pinfunction "A_A") (pintype "passive"))
    )
    (net (code "168") (name "Net-(RN3B-1)") (class "Default")
      (node (ref "RN3") (pin "2") (pinfunction "1_2") (pintype "passive"))
      (node (ref "TX") (pin "A") (pinfunction "A_A") (pintype "passive"))
    )
    (net (code "169") (name "Net-(RN3C-1)") (class "Default")
      (node (ref "L") (pin "A") (pinfunction "A_A") (pintype "passive"))
      (node (ref "RN3") (pin "3") (pinfunction "1_3") (pintype "passive"))
    )
    (net (code "170") (name "Net-(RN3D-1)") (class "Default")
      (node (ref "ON") (pin "A") (pinfunction "A_A") (pintype "passive"))
      (node (ref "RN3") (pin "4") (pinfunction "1_4") (pintype "passive"))
    )
    (net (code "171") (name "Net-(U1-DFSDM)") (class "Default")
      (node (ref "R5") (pin "2") (pinfunction "2_2") (pintype "passive"))
      (node (ref "U1") (pin "43") (pinfunction "DFSDM_43") (pintype "passive"))
    )
    (net (code "172") (name "Net-(U1-DFSDP)") (class "Default")
      (node (ref "R6") (pin "2") (pinfunction "2_2") (pintype "passive"))
      (node (ref "U1") (pin "42") (pinfunction "DFSDP_42") (pintype "passive"))
    )
    (net (code "173") (name "Net-(U1-FWUP)") (class "Default")
      (node (ref "R4") (pin "1") (pinfunction "1_1") (pintype "passive"))
      (node (ref "U1") (pin "53") (pinfunction "FWUP_53") (pintype "passive"))
    )
    (net (code "174") (name "Net-(U1-TST)") (class "Default")
      (node (ref "R8") (pin "2") (pinfunction "2_2") (pintype "passive"))
      (node (ref "U1") (pin "51") (pinfunction "TST_51") (pintype "passive"))
    )
    (net (code "175") (name "unconnected-(IC6-(AIN0{slash}INT1)PD1-Pad7)") (class "Default")
      (node (ref "IC6") (pin "7") (pinfunction "(AIN0/INT1)PD1_7") (pintype "passive+no_connect"))
    )
    (net (code "176") (name "unconnected-(IC6-(AIN2{slash}PCINT11)PC2-Pad5)") (class "Default")
      (node (ref "IC6") (pin "5") (pinfunction "(AIN2/PCINT11)PC2_5") (pintype "passive+no_connect"))
    )
    (net (code "177") (name "unconnected-(IC6-(OC0B{slash}INT0)PD0-Pad6)") (class "Default")
      (node (ref "IC6") (pin "6") (pinfunction "(OC0B/INT0)PD0_6") (pintype "passive+no_connect"))
    )
    (net (code "178") (name "unconnected-(IC6-(PCINT9{slash}OC1B)PC5-Pad25)") (class "Default")
      (node (ref "IC6") (pin "25") (pinfunction "(PCINT9/OC1B)PC5_25") (pintype "passive"))
    )
    (net (code "179") (name "unconnected-(IC6-(RTS{slash}AIN5{slash}INT6)PD6-Pad12)") (class "Default")
      (node (ref "IC6") (pin "12") (pinfunction "(RTS/AIN5/INT6)PD6_12") (pintype "passive+no_connect"))
    )
    (net (code "180") (name "unconnected-(IC6-(SS{slash}PCINT0)PB0-Pad14)") (class "Default")
      (node (ref "IC6") (pin "14") (pinfunction "(SS/PCINT0)PB0_14") (pintype "passive+no_connect"))
    )
    (net (code "181") (name "unconnected-(J3-ID-PadP4)") (class "Default")
      (node (ref "J3") (pin "P4") (pinfunction "ID_P4") (pintype "passive+no_connect"))
    )
    (net (code "182") (name "unconnected-(JTAG-Pad7)") (class "Default")
      (node (ref "JTAG") (pin "7") (pinfunction "7_7") (pintype "passive+no_connect"))
    )
    (net (code "183") (name "unconnected-(MACB-Pad4)") (class "Default")
      (node (ref "MACB") (pin "4") (pinfunction "4_4") (pintype "passive+no_connect"))
    )
    (net (code "184") (name "unconnected-(MACB-Pad6)") (class "Default")
      (node (ref "MACB") (pin "6") (pinfunction "6_6") (pintype "passive+no_connect"))
    )
    (net (code "185") (name "unconnected-(RESET-5-GND-Pad5)") (class "Default")
      (node (ref "RESET") (pin "5") (pinfunction "5-GND_5") (pintype "passive+no_connect"))
    )
    (net (code "186") (name "unconnected-(RN5C-1-Pad3)") (class "Default")
      (node (ref "RN5") (pin "3") (pinfunction "1_3") (pintype "passive+no_connect"))
    )
    (net (code "187") (name "unconnected-(RN5C-2-Pad6)") (class "Default")
      (node (ref "RN5") (pin "6") (pinfunction "2_6") (pintype "passive+no_connect"))
    )
    (net (code "188") (name "unconnected-(RN5D-1-Pad4)") (class "Default")
      (node (ref "RN5") (pin "4") (pinfunction "1_4") (pintype "passive+no_connect"))
    )
    (net (code "189") (name "unconnected-(RN5D-2-Pad5)") (class "Default")
      (node (ref "RN5") (pin "5") (pinfunction "2_5") (pintype "passive+no_connect"))
    )
    (net (code "190") (name "unconnected-(U1-NRST-Pad69)") (class "Default")
      (node (ref "U1") (pin "69") (pinfunction "NRST_69") (pintype "passive+no_connect"))
    )
    (net (code "191") (name "unconnected-(U1-PB22-Pad141)") (class "Default")
      (node (ref "U1") (pin "141") (pinfunction "PB22_141") (pintype "passive"))
    )
    (net (code "192") (name "unconnected-(U1-PB24-Pad143)") (class "Default")
      (node (ref "U1") (pin "143") (pinfunction "PB24_143") (pintype "passive"))
    )
    (net (code "193") (name "unconnected-(U1-PC10-Pad117)") (class "Default")
      (node (ref "U1") (pin "117") (pinfunction "PC10_117") (pintype "passive"))
    )
    (net (code "194") (name "unconnected-(U1-PC11-Pad93)") (class "Default")
      (node (ref "U1") (pin "93") (pinfunction "PC11_93") (pintype "passive"))
    )
    (net (code "195") (name "unconnected-(U1-PC20-Pad131)") (class "Default")
      (node (ref "U1") (pin "131") (pinfunction "PC20_131") (pintype "passive"))
    )
    (net (code "196") (name "unconnected-(U1-PC27-Pad138)") (class "Default")
      (node (ref "U1") (pin "138") (pinfunction "PC27_138") (pintype "passive"))
    )
    (net (code "197") (name "unconnected-(U1-SHDN-Pad50)") (class "Default")
      (node (ref "U1") (pin "50") (pinfunction "SHDN_50") (pintype "passive+no_connect"))
    )
  )
)
